# LEDpanel.net
KiCad netlist of a schematic drawn in EAGLE
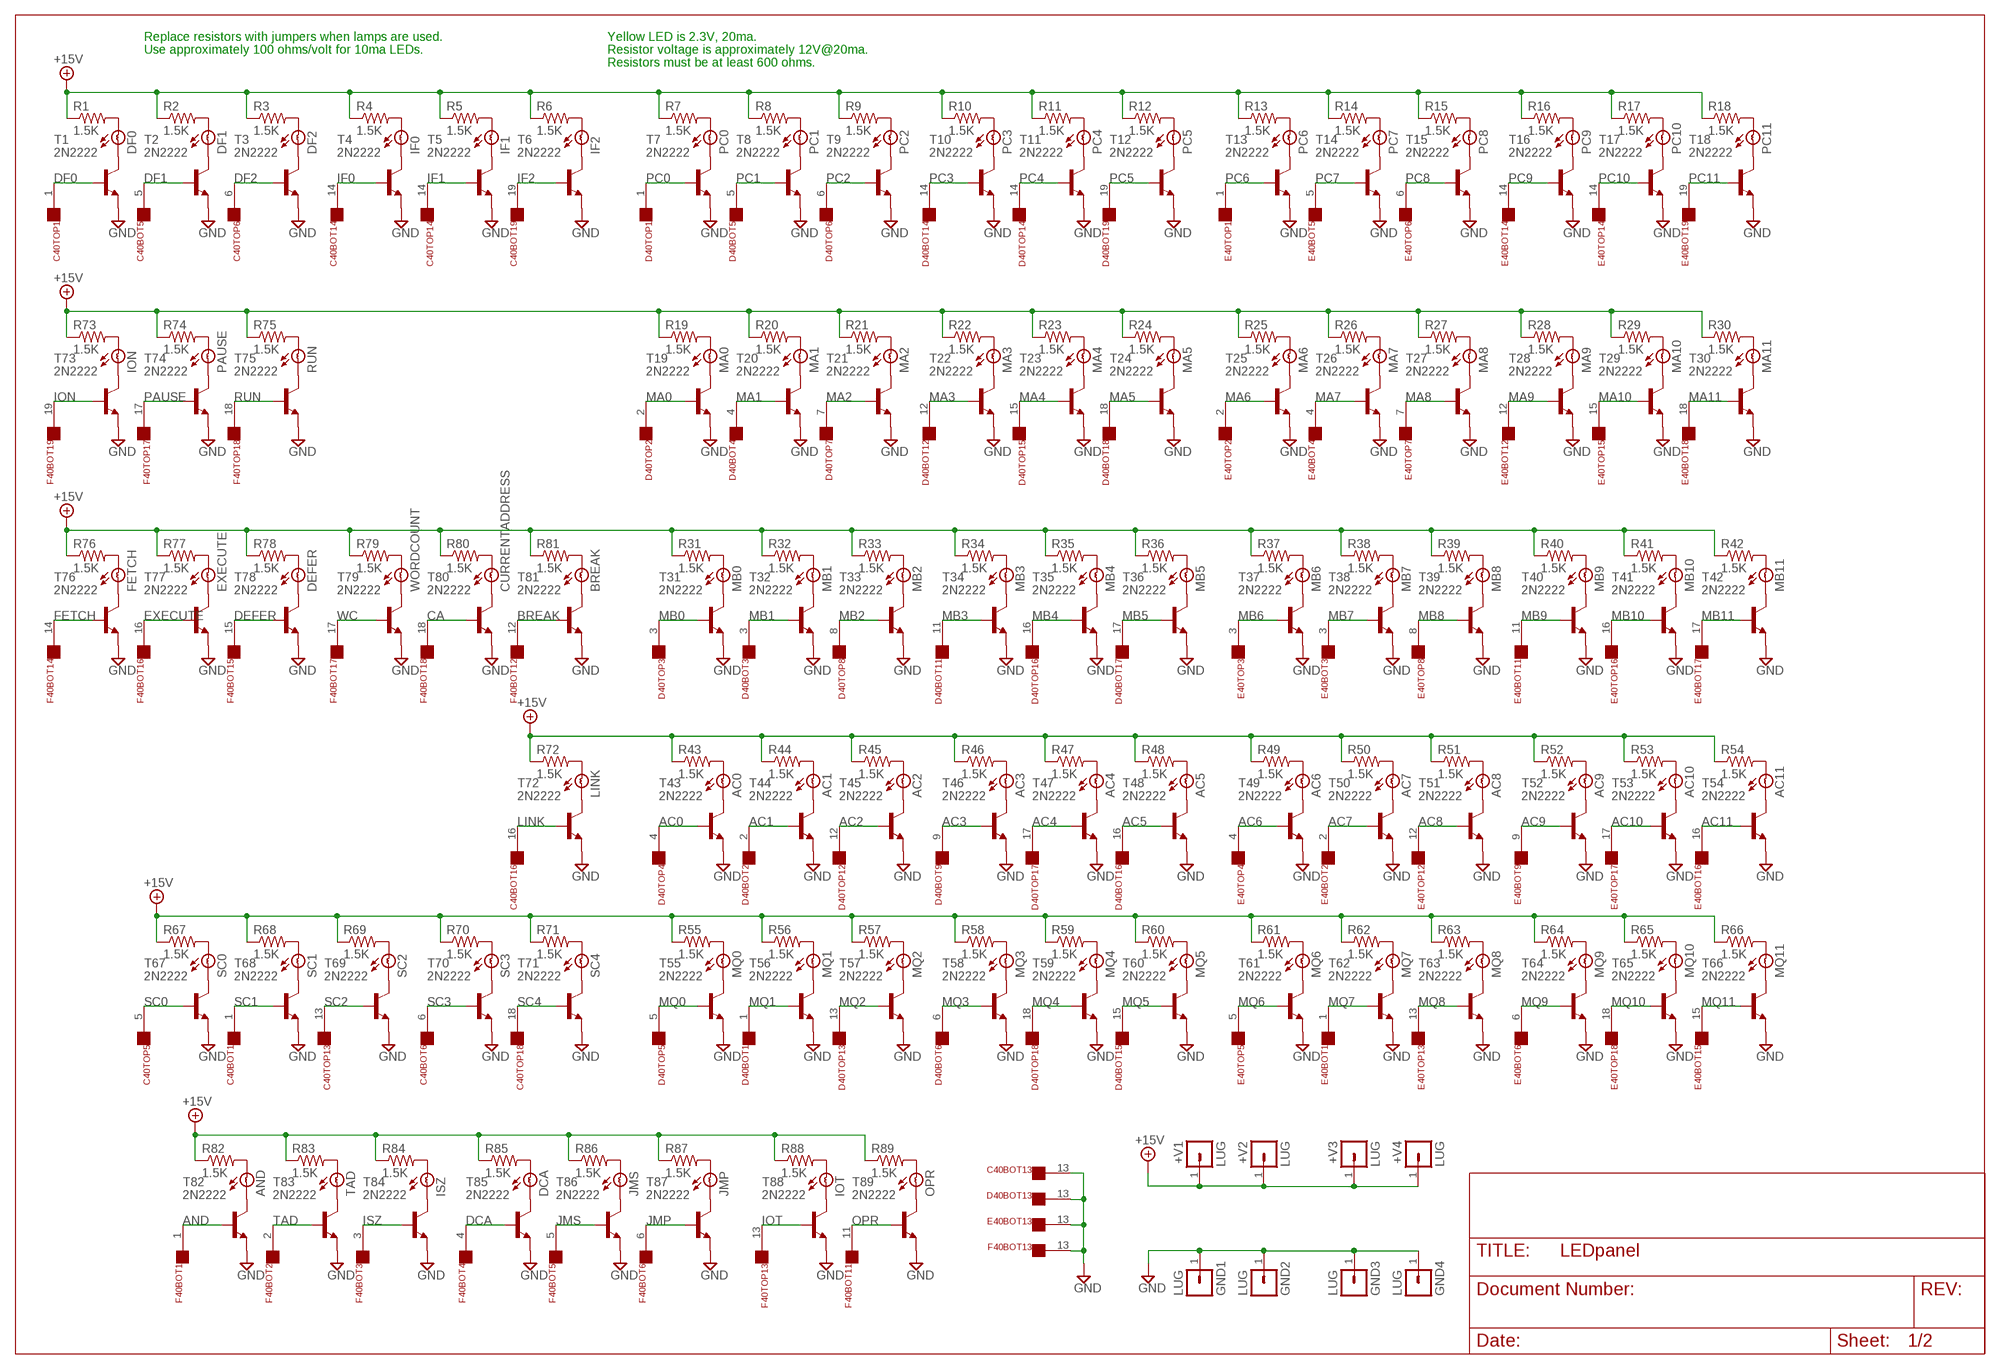
[diagram p0: schematic, sheet 1]
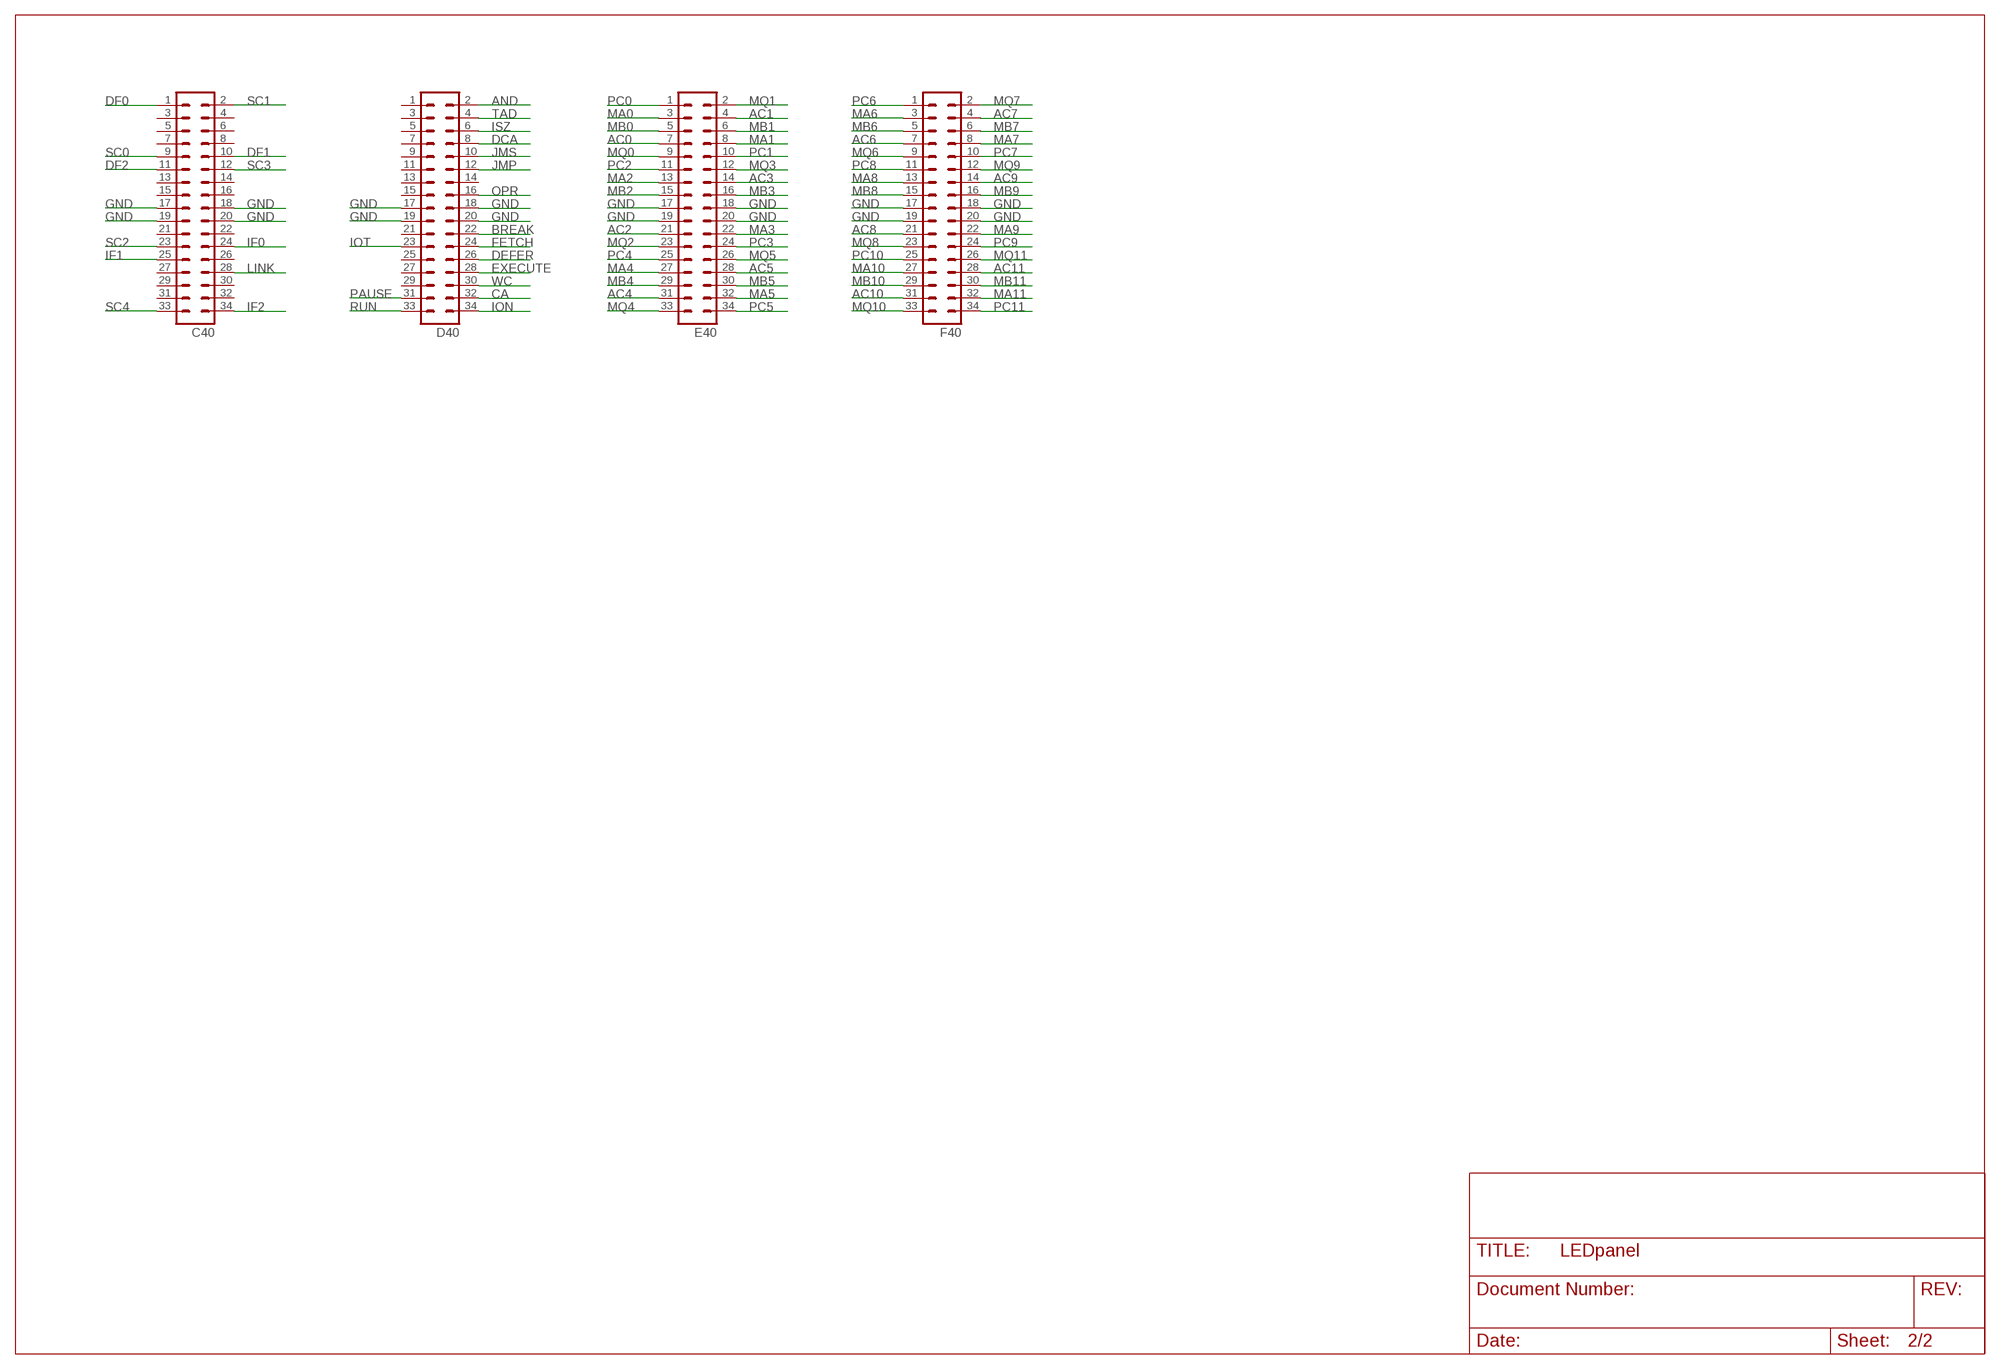
[diagram p1: schematic, sheet 2]

(export (version "E")
  (design (tool "Eeschema 10.0.6"))
  (components
    (comp (ref "+V1")
      (value "LUG")
      (footprint "eagle-import:SPADELUG")
      (libsource (lib "eagle-import") (part "LUG"))
    )
    (comp (ref "+V2")
      (value "LUG")
      (footprint "eagle-import:SPADELUG")
      (libsource (lib "eagle-import") (part "LUG"))
    )
    (comp (ref "+V3")
      (value "LUG")
      (footprint "eagle-import:SPADELUG")
      (libsource (lib "eagle-import") (part "LUG"))
    )
    (comp (ref "+V4")
      (value "LUG")
      (footprint "eagle-import:SPADELUG")
      (libsource (lib "eagle-import") (part "LUG"))
    )
    (comp (ref "AC0")
      (value "BULB")
      (footprint "eagle-import:BULB")
      (libsource (lib "eagle-import") (part "BULB"))
    )
    (comp (ref "AC1")
      (value "BULB")
      (footprint "eagle-import:BULB")
      (libsource (lib "eagle-import") (part "BULB"))
    )
    (comp (ref "AC2")
      (value "BULB")
      (footprint "eagle-import:BULB")
      (libsource (lib "eagle-import") (part "BULB"))
    )
    (comp (ref "AC3")
      (value "BULB")
      (footprint "eagle-import:BULB")
      (libsource (lib "eagle-import") (part "BULB"))
    )
    (comp (ref "AC4")
      (value "BULB")
      (footprint "eagle-import:BULB")
      (libsource (lib "eagle-import") (part "BULB"))
    )
    (comp (ref "AC5")
      (value "BULB")
      (footprint "eagle-import:BULB")
      (libsource (lib "eagle-import") (part "BULB"))
    )
    (comp (ref "AC6")
      (value "BULB")
      (footprint "eagle-import:BULB")
      (libsource (lib "eagle-import") (part "BULB"))
    )
    (comp (ref "AC7")
      (value "BULB")
      (footprint "eagle-import:BULB")
      (libsource (lib "eagle-import") (part "BULB"))
    )
    (comp (ref "AC8")
      (value "BULB")
      (footprint "eagle-import:BULB")
      (libsource (lib "eagle-import") (part "BULB"))
    )
    (comp (ref "AC9")
      (value "BULB")
      (footprint "eagle-import:BULB")
      (libsource (lib "eagle-import") (part "BULB"))
    )
    (comp (ref "AC10")
      (value "BULB")
      (footprint "eagle-import:BULB")
      (libsource (lib "eagle-import") (part "BULB"))
    )
    (comp (ref "AC11")
      (value "BULB")
      (footprint "eagle-import:BULB")
      (libsource (lib "eagle-import") (part "BULB"))
    )
    (comp (ref "AND")
      (value "BULB")
      (footprint "eagle-import:BULB")
      (libsource (lib "eagle-import") (part "BULB"))
    )
    (comp (ref "BREAK")
      (value "BULB")
      (footprint "eagle-import:BULB")
      (libsource (lib "eagle-import") (part "BULB"))
    )
    (comp (ref "C40BOT")
      (value "FLEX19")
      (footprint "eagle-import:FLEX19")
      (libsource (lib "eagle-import") (part "FLEX19"))
    )
    (comp (ref "C40TOP")
      (value "FLEX19")
      (footprint "eagle-import:FLEX19")
      (libsource (lib "eagle-import") (part "FLEX19"))
    )
    (comp (ref "CURRENTADDRESS")
      (value "BULB")
      (footprint "eagle-import:BULB")
      (libsource (lib "eagle-import") (part "BULB"))
    )
    (comp (ref "D40BOT")
      (value "FLEX19")
      (footprint "eagle-import:FLEX19")
      (libsource (lib "eagle-import") (part "FLEX19"))
    )
    (comp (ref "D40TOP")
      (value "FLEX19")
      (footprint "eagle-import:FLEX19")
      (libsource (lib "eagle-import") (part "FLEX19"))
    )
    (comp (ref "DCA")
      (value "BULB")
      (footprint "eagle-import:BULB")
      (libsource (lib "eagle-import") (part "BULB"))
    )
    (comp (ref "DEFER")
      (value "BULB")
      (footprint "eagle-import:BULB")
      (libsource (lib "eagle-import") (part "BULB"))
    )
    (comp (ref "DF0")
      (value "BULB")
      (footprint "eagle-import:BULB")
      (libsource (lib "eagle-import") (part "BULB"))
    )
    (comp (ref "DF1")
      (value "BULB")
      (footprint "eagle-import:BULB")
      (libsource (lib "eagle-import") (part "BULB"))
    )
    (comp (ref "DF2")
      (value "BULB")
      (footprint "eagle-import:BULB")
      (libsource (lib "eagle-import") (part "BULB"))
    )
    (comp (ref "E40BOT")
      (value "FLEX19")
      (footprint "eagle-import:FLEX19")
      (libsource (lib "eagle-import") (part "FLEX19"))
    )
    (comp (ref "E40TOP")
      (value "FLEX19")
      (footprint "eagle-import:FLEX19")
      (libsource (lib "eagle-import") (part "FLEX19"))
    )
    (comp (ref "EXECUTE")
      (value "BULB")
      (footprint "eagle-import:BULB")
      (libsource (lib "eagle-import") (part "BULB"))
    )
    (comp (ref "F40BOT")
      (value "FLEX19")
      (footprint "eagle-import:FLEX19")
      (libsource (lib "eagle-import") (part "FLEX19"))
    )
    (comp (ref "F40TOP")
      (value "FLEX19")
      (footprint "eagle-import:FLEX19")
      (libsource (lib "eagle-import") (part "FLEX19"))
    )
    (comp (ref "FETCH")
      (value "BULB")
      (footprint "eagle-import:BULB")
      (libsource (lib "eagle-import") (part "BULB"))
    )
    (comp (ref "GND1")
      (value "LUG")
      (footprint "eagle-import:SPADELUG")
      (libsource (lib "eagle-import") (part "LUG"))
    )
    (comp (ref "GND2")
      (value "LUG")
      (footprint "eagle-import:SPADELUG")
      (libsource (lib "eagle-import") (part "LUG"))
    )
    (comp (ref "GND3")
      (value "LUG")
      (footprint "eagle-import:SPADELUG")
      (libsource (lib "eagle-import") (part "LUG"))
    )
    (comp (ref "GND4")
      (value "LUG")
      (footprint "eagle-import:SPADELUG")
      (libsource (lib "eagle-import") (part "LUG"))
    )
    (comp (ref "IF0")
      (value "BULB")
      (footprint "eagle-import:BULB")
      (libsource (lib "eagle-import") (part "BULB"))
    )
    (comp (ref "IF1")
      (value "BULB")
      (footprint "eagle-import:BULB")
      (libsource (lib "eagle-import") (part "BULB"))
    )
    (comp (ref "IF2")
      (value "BULB")
      (footprint "eagle-import:BULB")
      (libsource (lib "eagle-import") (part "BULB"))
    )
    (comp (ref "ION")
      (value "BULB")
      (footprint "eagle-import:BULB")
      (libsource (lib "eagle-import") (part "BULB"))
    )
    (comp (ref "IOT")
      (value "BULB")
      (footprint "eagle-import:BULB")
      (libsource (lib "eagle-import") (part "BULB"))
    )
    (comp (ref "ISZ")
      (value "BULB")
      (footprint "eagle-import:BULB")
      (libsource (lib "eagle-import") (part "BULB"))
    )
    (comp (ref "JMP")
      (value "BULB")
      (footprint "eagle-import:BULB")
      (libsource (lib "eagle-import") (part "BULB"))
    )
    (comp (ref "JMS")
      (value "BULB")
      (footprint "eagle-import:BULB")
      (libsource (lib "eagle-import") (part "BULB"))
    )
    (comp (ref "LINK")
      (value "BULB")
      (footprint "eagle-import:BULB")
      (libsource (lib "eagle-import") (part "BULB"))
    )
    (comp (ref "MA0")
      (value "BULB")
      (footprint "eagle-import:BULB")
      (libsource (lib "eagle-import") (part "BULB"))
    )
    (comp (ref "MA1")
      (value "BULB")
      (footprint "eagle-import:BULB")
      (libsource (lib "eagle-import") (part "BULB"))
    )
    (comp (ref "MA2")
      (value "BULB")
      (footprint "eagle-import:BULB")
      (libsource (lib "eagle-import") (part "BULB"))
    )
    (comp (ref "MA3")
      (value "BULB")
      (footprint "eagle-import:BULB")
      (libsource (lib "eagle-import") (part "BULB"))
    )
    (comp (ref "MA4")
      (value "BULB")
      (footprint "eagle-import:BULB")
      (libsource (lib "eagle-import") (part "BULB"))
    )
    (comp (ref "MA5")
      (value "BULB")
      (footprint "eagle-import:BULB")
      (libsource (lib "eagle-import") (part "BULB"))
    )
    (comp (ref "MA6")
      (value "BULB")
      (footprint "eagle-import:BULB")
      (libsource (lib "eagle-import") (part "BULB"))
    )
    (comp (ref "MA7")
      (value "BULB")
      (footprint "eagle-import:BULB")
      (libsource (lib "eagle-import") (part "BULB"))
    )
    (comp (ref "MA8")
      (value "BULB")
      (footprint "eagle-import:BULB")
      (libsource (lib "eagle-import") (part "BULB"))
    )
    (comp (ref "MA9")
      (value "BULB")
      (footprint "eagle-import:BULB")
      (libsource (lib "eagle-import") (part "BULB"))
    )
    (comp (ref "MA10")
      (value "BULB")
      (footprint "eagle-import:BULB")
      (libsource (lib "eagle-import") (part "BULB"))
    )
    (comp (ref "MA11")
      (value "BULB")
      (footprint "eagle-import:BULB")
      (libsource (lib "eagle-import") (part "BULB"))
    )
    (comp (ref "MB0")
      (value "BULB")
      (footprint "eagle-import:BULB")
      (libsource (lib "eagle-import") (part "BULB"))
    )
    (comp (ref "MB1")
      (value "BULB")
      (footprint "eagle-import:BULB")
      (libsource (lib "eagle-import") (part "BULB"))
    )
    (comp (ref "MB2")
      (value "BULB")
      (footprint "eagle-import:BULB")
      (libsource (lib "eagle-import") (part "BULB"))
    )
    (comp (ref "MB3")
      (value "BULB")
      (footprint "eagle-import:BULB")
      (libsource (lib "eagle-import") (part "BULB"))
    )
    (comp (ref "MB4")
      (value "BULB")
      (footprint "eagle-import:BULB")
      (libsource (lib "eagle-import") (part "BULB"))
    )
    (comp (ref "MB5")
      (value "BULB")
      (footprint "eagle-import:BULB")
      (libsource (lib "eagle-import") (part "BULB"))
    )
    (comp (ref "MB6")
      (value "BULB")
      (footprint "eagle-import:BULB")
      (libsource (lib "eagle-import") (part "BULB"))
    )
    (comp (ref "MB7")
      (value "BULB")
      (footprint "eagle-import:BULB")
      (libsource (lib "eagle-import") (part "BULB"))
    )
    (comp (ref "MB8")
      (value "BULB")
      (footprint "eagle-import:BULB")
      (libsource (lib "eagle-import") (part "BULB"))
    )
    (comp (ref "MB9")
      (value "BULB")
      (footprint "eagle-import:BULB")
      (libsource (lib "eagle-import") (part "BULB"))
    )
    (comp (ref "MB10")
      (value "BULB")
      (footprint "eagle-import:BULB")
      (libsource (lib "eagle-import") (part "BULB"))
    )
    (comp (ref "MB11")
      (value "BULB")
      (footprint "eagle-import:BULB")
      (libsource (lib "eagle-import") (part "BULB"))
    )
    (comp (ref "MQ0")
      (value "BULB")
      (footprint "eagle-import:BULB")
      (libsource (lib "eagle-import") (part "BULB"))
    )
    (comp (ref "MQ1")
      (value "BULB")
      (footprint "eagle-import:BULB")
      (libsource (lib "eagle-import") (part "BULB"))
    )
    (comp (ref "MQ2")
      (value "BULB")
      (footprint "eagle-import:BULB")
      (libsource (lib "eagle-import") (part "BULB"))
    )
    (comp (ref "MQ3")
      (value "BULB")
      (footprint "eagle-import:BULB")
      (libsource (lib "eagle-import") (part "BULB"))
    )
    (comp (ref "MQ4")
      (value "BULB")
      (footprint "eagle-import:BULB")
      (libsource (lib "eagle-import") (part "BULB"))
    )
    (comp (ref "MQ5")
      (value "BULB")
      (footprint "eagle-import:BULB")
      (libsource (lib "eagle-import") (part "BULB"))
    )
    (comp (ref "MQ6")
      (value "BULB")
      (footprint "eagle-import:BULB")
      (libsource (lib "eagle-import") (part "BULB"))
    )
    (comp (ref "MQ7")
      (value "BULB")
      (footprint "eagle-import:BULB")
      (libsource (lib "eagle-import") (part "BULB"))
    )
    (comp (ref "MQ8")
      (value "BULB")
      (footprint "eagle-import:BULB")
      (libsource (lib "eagle-import") (part "BULB"))
    )
    (comp (ref "MQ9")
      (value "BULB")
      (footprint "eagle-import:BULB")
      (libsource (lib "eagle-import") (part "BULB"))
    )
    (comp (ref "MQ10")
      (value "BULB")
      (footprint "eagle-import:BULB")
      (libsource (lib "eagle-import") (part "BULB"))
    )
    (comp (ref "MQ11")
      (value "BULB")
      (footprint "eagle-import:BULB")
      (libsource (lib "eagle-import") (part "BULB"))
    )
    (comp (ref "OPR")
      (value "BULB")
      (footprint "eagle-import:BULB")
      (libsource (lib "eagle-import") (part "BULB"))
    )
    (comp (ref "PAUSE")
      (value "BULB")
      (footprint "eagle-import:BULB")
      (libsource (lib "eagle-import") (part "BULB"))
    )
    (comp (ref "PC0")
      (value "BULB")
      (footprint "eagle-import:BULB")
      (libsource (lib "eagle-import") (part "BULB"))
    )
    (comp (ref "PC1")
      (value "BULB")
      (footprint "eagle-import:BULB")
      (libsource (lib "eagle-import") (part "BULB"))
    )
    (comp (ref "PC2")
      (value "BULB")
      (footprint "eagle-import:BULB")
      (libsource (lib "eagle-import") (part "BULB"))
    )
    (comp (ref "PC3")
      (value "BULB")
      (footprint "eagle-import:BULB")
      (libsource (lib "eagle-import") (part "BULB"))
    )
    (comp (ref "PC4")
      (value "BULB")
      (footprint "eagle-import:BULB")
      (libsource (lib "eagle-import") (part "BULB"))
    )
    (comp (ref "PC5")
      (value "BULB")
      (footprint "eagle-import:BULB")
      (libsource (lib "eagle-import") (part "BULB"))
    )
    (comp (ref "PC6")
      (value "BULB")
      (footprint "eagle-import:BULB")
      (libsource (lib "eagle-import") (part "BULB"))
    )
    (comp (ref "PC7")
      (value "BULB")
      (footprint "eagle-import:BULB")
      (libsource (lib "eagle-import") (part "BULB"))
    )
    (comp (ref "PC8")
      (value "BULB")
      (footprint "eagle-import:BULB")
      (libsource (lib "eagle-import") (part "BULB"))
    )
    (comp (ref "PC9")
      (value "BULB")
      (footprint "eagle-import:BULB")
      (libsource (lib "eagle-import") (part "BULB"))
    )
    (comp (ref "PC10")
      (value "BULB")
      (footprint "eagle-import:BULB")
      (libsource (lib "eagle-import") (part "BULB"))
    )
    (comp (ref "PC11")
      (value "BULB")
      (footprint "eagle-import:BULB")
      (libsource (lib "eagle-import") (part "BULB"))
    )
    (comp (ref "R1")
      (value "1.5K")
      (footprint "eagle-import:0207_10")
      (libsource (lib "eagle-import") (part "R-US_0207/10"))
    )
    (comp (ref "R2")
      (value "1.5K")
      (footprint "eagle-import:0207_10")
      (libsource (lib "eagle-import") (part "R-US_0207/10"))
    )
    (comp (ref "R3")
      (value "1.5K")
      (footprint "eagle-import:0207_10")
      (libsource (lib "eagle-import") (part "R-US_0207/10"))
    )
    (comp (ref "R4")
      (value "1.5K")
      (footprint "eagle-import:0207_10")
      (libsource (lib "eagle-import") (part "R-US_0207/10"))
    )
    (comp (ref "R5")
      (value "1.5K")
      (footprint "eagle-import:0207_10")
      (libsource (lib "eagle-import") (part "R-US_0207/10"))
    )
    (comp (ref "R6")
      (value "1.5K")
      (footprint "eagle-import:0207_10")
      (libsource (lib "eagle-import") (part "R-US_0207/10"))
    )
    (comp (ref "R7")
      (value "1.5K")
      (footprint "eagle-import:0207_10")
      (libsource (lib "eagle-import") (part "R-US_0207/10"))
    )
    (comp (ref "R8")
      (value "1.5K")
      (footprint "eagle-import:0207_10")
      (libsource (lib "eagle-import") (part "R-US_0207/10"))
    )
    (comp (ref "R9")
      (value "1.5K")
      (footprint "eagle-import:0207_10")
      (libsource (lib "eagle-import") (part "R-US_0207/10"))
    )
    (comp (ref "R10")
      (value "1.5K")
      (footprint "eagle-import:0207_10")
      (libsource (lib "eagle-import") (part "R-US_0207/10"))
    )
    (comp (ref "R11")
      (value "1.5K")
      (footprint "eagle-import:0207_10")
      (libsource (lib "eagle-import") (part "R-US_0207/10"))
    )
    (comp (ref "R12")
      (value "1.5K")
      (footprint "eagle-import:0207_10")
      (libsource (lib "eagle-import") (part "R-US_0207/10"))
    )
    (comp (ref "R13")
      (value "1.5K")
      (footprint "eagle-import:0207_10")
      (libsource (lib "eagle-import") (part "R-US_0207/10"))
    )
    (comp (ref "R14")
      (value "1.5K")
      (footprint "eagle-import:0207_10")
      (libsource (lib "eagle-import") (part "R-US_0207/10"))
    )
    (comp (ref "R15")
      (value "1.5K")
      (footprint "eagle-import:0207_10")
      (libsource (lib "eagle-import") (part "R-US_0207/10"))
    )
    (comp (ref "R16")
      (value "1.5K")
      (footprint "eagle-import:0207_10")
      (libsource (lib "eagle-import") (part "R-US_0207/10"))
    )
    (comp (ref "R17")
      (value "1.5K")
      (footprint "eagle-import:0207_10")
      (libsource (lib "eagle-import") (part "R-US_0207/10"))
    )
    (comp (ref "R18")
      (value "1.5K")
      (footprint "eagle-import:0207_10")
      (libsource (lib "eagle-import") (part "R-US_0207/10"))
    )
    (comp (ref "R19")
      (value "1.5K")
      (footprint "eagle-import:0207_10")
      (libsource (lib "eagle-import") (part "R-US_0207/10"))
    )
    (comp (ref "R20")
      (value "1.5K")
      (footprint "eagle-import:0207_10")
      (libsource (lib "eagle-import") (part "R-US_0207/10"))
    )
    (comp (ref "R21")
      (value "1.5K")
      (footprint "eagle-import:0207_10")
      (libsource (lib "eagle-import") (part "R-US_0207/10"))
    )
    (comp (ref "R22")
      (value "1.5K")
      (footprint "eagle-import:0207_10")
      (libsource (lib "eagle-import") (part "R-US_0207/10"))
    )
    (comp (ref "R23")
      (value "1.5K")
      (footprint "eagle-import:0207_10")
      (libsource (lib "eagle-import") (part "R-US_0207/10"))
    )
    (comp (ref "R24")
      (value "1.5K")
      (footprint "eagle-import:0207_10")
      (libsource (lib "eagle-import") (part "R-US_0207/10"))
    )
    (comp (ref "R25")
      (value "1.5K")
      (footprint "eagle-import:0207_10")
      (libsource (lib "eagle-import") (part "R-US_0207/10"))
    )
    (comp (ref "R26")
      (value "1.5K")
      (footprint "eagle-import:0207_10")
      (libsource (lib "eagle-import") (part "R-US_0207/10"))
    )
    (comp (ref "R27")
      (value "1.5K")
      (footprint "eagle-import:0207_10")
      (libsource (lib "eagle-import") (part "R-US_0207/10"))
    )
    (comp (ref "R28")
      (value "1.5K")
      (footprint "eagle-import:0207_10")
      (libsource (lib "eagle-import") (part "R-US_0207/10"))
    )
    (comp (ref "R29")
      (value "1.5K")
      (footprint "eagle-import:0207_10")
      (libsource (lib "eagle-import") (part "R-US_0207/10"))
    )
    (comp (ref "R30")
      (value "1.5K")
      (footprint "eagle-import:0207_10")
      (libsource (lib "eagle-import") (part "R-US_0207/10"))
    )
    (comp (ref "R31")
      (value "1.5K")
      (footprint "eagle-import:0207_10")
      (libsource (lib "eagle-import") (part "R-US_0207/10"))
    )
    (comp (ref "R32")
      (value "1.5K")
      (footprint "eagle-import:0207_10")
      (libsource (lib "eagle-import") (part "R-US_0207/10"))
    )
    (comp (ref "R33")
      (value "1.5K")
      (footprint "eagle-import:0207_10")
      (libsource (lib "eagle-import") (part "R-US_0207/10"))
    )
    (comp (ref "R34")
      (value "1.5K")
      (footprint "eagle-import:0207_10")
      (libsource (lib "eagle-import") (part "R-US_0207/10"))
    )
    (comp (ref "R35")
      (value "1.5K")
      (footprint "eagle-import:0207_10")
      (libsource (lib "eagle-import") (part "R-US_0207/10"))
    )
    (comp (ref "R36")
      (value "1.5K")
      (footprint "eagle-import:0207_10")
      (libsource (lib "eagle-import") (part "R-US_0207/10"))
    )
    (comp (ref "R37")
      (value "1.5K")
      (footprint "eagle-import:0207_10")
      (libsource (lib "eagle-import") (part "R-US_0207/10"))
    )
    (comp (ref "R38")
      (value "1.5K")
      (footprint "eagle-import:0207_10")
      (libsource (lib "eagle-import") (part "R-US_0207/10"))
    )
    (comp (ref "R39")
      (value "1.5K")
      (footprint "eagle-import:0207_10")
      (libsource (lib "eagle-import") (part "R-US_0207/10"))
    )
    (comp (ref "R40")
      (value "1.5K")
      (footprint "eagle-import:0207_10")
      (libsource (lib "eagle-import") (part "R-US_0207/10"))
    )
    (comp (ref "R41")
      (value "1.5K")
      (footprint "eagle-import:0207_10")
      (libsource (lib "eagle-import") (part "R-US_0207/10"))
    )
    (comp (ref "R42")
      (value "1.5K")
      (footprint "eagle-import:0207_10")
      (libsource (lib "eagle-import") (part "R-US_0207/10"))
    )
    (comp (ref "R43")
      (value "1.5K")
      (footprint "eagle-import:0207_10")
      (libsource (lib "eagle-import") (part "R-US_0207/10"))
    )
    (comp (ref "R44")
      (value "1.5K")
      (footprint "eagle-import:0207_10")
      (libsource (lib "eagle-import") (part "R-US_0207/10"))
    )
    (comp (ref "R45")
      (value "1.5K")
      (footprint "eagle-import:0207_10")
      (libsource (lib "eagle-import") (part "R-US_0207/10"))
    )
    (comp (ref "R46")
      (value "1.5K")
      (footprint "eagle-import:0207_10")
      (libsource (lib "eagle-import") (part "R-US_0207/10"))
    )
    (comp (ref "R47")
      (value "1.5K")
      (footprint "eagle-import:0207_10")
      (libsource (lib "eagle-import") (part "R-US_0207/10"))
    )
    (comp (ref "R48")
      (value "1.5K")
      (footprint "eagle-import:0207_10")
      (libsource (lib "eagle-import") (part "R-US_0207/10"))
    )
    (comp (ref "R49")
      (value "1.5K")
      (footprint "eagle-import:0207_10")
      (libsource (lib "eagle-import") (part "R-US_0207/10"))
    )
    (comp (ref "R50")
      (value "1.5K")
      (footprint "eagle-import:0207_10")
      (libsource (lib "eagle-import") (part "R-US_0207/10"))
    )
    (comp (ref "R51")
      (value "1.5K")
      (footprint "eagle-import:0207_10")
      (libsource (lib "eagle-import") (part "R-US_0207/10"))
    )
    (comp (ref "R52")
      (value "1.5K")
      (footprint "eagle-import:0207_10")
      (libsource (lib "eagle-import") (part "R-US_0207/10"))
    )
    (comp (ref "R53")
      (value "1.5K")
      (footprint "eagle-import:0207_10")
      (libsource (lib "eagle-import") (part "R-US_0207/10"))
    )
    (comp (ref "R54")
      (value "1.5K")
      (footprint "eagle-import:0207_10")
      (libsource (lib "eagle-import") (part "R-US_0207/10"))
    )
    (comp (ref "R55")
      (value "1.5K")
      (footprint "eagle-import:0207_10")
      (libsource (lib "eagle-import") (part "R-US_0207/10"))
    )
    (comp (ref "R56")
      (value "1.5K")
      (footprint "eagle-import:0207_10")
      (libsource (lib "eagle-import") (part "R-US_0207/10"))
    )
    (comp (ref "R57")
      (value "1.5K")
      (footprint "eagle-import:0207_10")
      (libsource (lib "eagle-import") (part "R-US_0207/10"))
    )
    (comp (ref "R58")
      (value "1.5K")
      (footprint "eagle-import:0207_10")
      (libsource (lib "eagle-import") (part "R-US_0207/10"))
    )
    (comp (ref "R59")
      (value "1.5K")
      (footprint "eagle-import:0207_10")
      (libsource (lib "eagle-import") (part "R-US_0207/10"))
    )
    (comp (ref "R60")
      (value "1.5K")
      (footprint "eagle-import:0207_10")
      (libsource (lib "eagle-import") (part "R-US_0207/10"))
    )
    (comp (ref "R61")
      (value "1.5K")
      (footprint "eagle-import:0207_10")
      (libsource (lib "eagle-import") (part "R-US_0207/10"))
    )
    (comp (ref "R62")
      (value "1.5K")
      (footprint "eagle-import:0207_10")
      (libsource (lib "eagle-import") (part "R-US_0207/10"))
    )
    (comp (ref "R63")
      (value "1.5K")
      (footprint "eagle-import:0207_10")
      (libsource (lib "eagle-import") (part "R-US_0207/10"))
    )
    (comp (ref "R64")
      (value "1.5K")
      (footprint "eagle-import:0207_10")
      (libsource (lib "eagle-import") (part "R-US_0207/10"))
    )
    (comp (ref "R65")
      (value "1.5K")
      (footprint "eagle-import:0207_10")
      (libsource (lib "eagle-import") (part "R-US_0207/10"))
    )
    (comp (ref "R66")
      (value "1.5K")
      (footprint "eagle-import:0207_10")
      (libsource (lib "eagle-import") (part "R-US_0207/10"))
    )
    (comp (ref "R67")
      (value "1.5K")
      (footprint "eagle-import:0207_10")
      (libsource (lib "eagle-import") (part "R-US_0207/10"))
    )
    (comp (ref "R68")
      (value "1.5K")
      (footprint "eagle-import:0207_10")
      (libsource (lib "eagle-import") (part "R-US_0207/10"))
    )
    (comp (ref "R69")
      (value "1.5K")
      (footprint "eagle-import:0207_10")
      (libsource (lib "eagle-import") (part "R-US_0207/10"))
    )
    (comp (ref "R70")
      (value "1.5K")
      (footprint "eagle-import:0207_10")
      (libsource (lib "eagle-import") (part "R-US_0207/10"))
    )
    (comp (ref "R71")
      (value "1.5K")
      (footprint "eagle-import:0207_10")
      (libsource (lib "eagle-import") (part "R-US_0207/10"))
    )
    (comp (ref "R72")
      (value "1.5K")
      (footprint "eagle-import:0207_10")
      (libsource (lib "eagle-import") (part "R-US_0207/10"))
    )
    (comp (ref "R73")
      (value "1.5K")
      (footprint "eagle-import:0207_10")
      (libsource (lib "eagle-import") (part "R-US_0207/10"))
    )
    (comp (ref "R74")
      (value "1.5K")
      (footprint "eagle-import:0207_10")
      (libsource (lib "eagle-import") (part "R-US_0207/10"))
    )
    (comp (ref "R75")
      (value "1.5K")
      (footprint "eagle-import:0207_10")
      (libsource (lib "eagle-import") (part "R-US_0207/10"))
    )
    (comp (ref "R76")
      (value "1.5K")
      (footprint "eagle-import:0207_10")
      (libsource (lib "eagle-import") (part "R-US_0207/10"))
    )
    (comp (ref "R77")
      (value "1.5K")
      (footprint "eagle-import:0207_10")
      (libsource (lib "eagle-import") (part "R-US_0207/10"))
    )
    (comp (ref "R78")
      (value "1.5K")
      (footprint "eagle-import:0207_10")
      (libsource (lib "eagle-import") (part "R-US_0207/10"))
    )
    (comp (ref "R79")
      (value "1.5K")
      (footprint "eagle-import:0207_10")
      (libsource (lib "eagle-import") (part "R-US_0207/10"))
    )
    (comp (ref "R80")
      (value "1.5K")
      (footprint "eagle-import:0207_10")
      (libsource (lib "eagle-import") (part "R-US_0207/10"))
    )
    (comp (ref "R81")
      (value "1.5K")
      (footprint "eagle-import:0207_10")
      (libsource (lib "eagle-import") (part "R-US_0207/10"))
    )
    (comp (ref "R82")
      (value "1.5K")
      (footprint "eagle-import:0207_10")
      (libsource (lib "eagle-import") (part "R-US_0207/10"))
    )
    (comp (ref "R83")
      (value "1.5K")
      (footprint "eagle-import:0207_10")
      (libsource (lib "eagle-import") (part "R-US_0207/10"))
    )
    (comp (ref "R84")
      (value "1.5K")
      (footprint "eagle-import:0207_10")
      (libsource (lib "eagle-import") (part "R-US_0207/10"))
    )
    (comp (ref "R85")
      (value "1.5K")
      (footprint "eagle-import:0207_10")
      (libsource (lib "eagle-import") (part "R-US_0207/10"))
    )
    (comp (ref "R86")
      (value "1.5K")
      (footprint "eagle-import:0207_10")
      (libsource (lib "eagle-import") (part "R-US_0207/10"))
    )
    (comp (ref "R87")
      (value "1.5K")
      (footprint "eagle-import:0207_10")
      (libsource (lib "eagle-import") (part "R-US_0207/10"))
    )
    (comp (ref "R88")
      (value "1.5K")
      (footprint "eagle-import:0207_10")
      (libsource (lib "eagle-import") (part "R-US_0207/10"))
    )
    (comp (ref "R89")
      (value "1.5K")
      (footprint "eagle-import:0207_10")
      (libsource (lib "eagle-import") (part "R-US_0207/10"))
    )
    (comp (ref "RUN")
      (value "BULB")
      (footprint "eagle-import:BULB")
      (libsource (lib "eagle-import") (part "BULB"))
    )
    (comp (ref "SC0")
      (value "BULB")
      (footprint "eagle-import:BULB")
      (libsource (lib "eagle-import") (part "BULB"))
    )
    (comp (ref "SC1")
      (value "BULB")
      (footprint "eagle-import:BULB")
      (libsource (lib "eagle-import") (part "BULB"))
    )
    (comp (ref "SC2")
      (value "BULB")
      (footprint "eagle-import:BULB")
      (libsource (lib "eagle-import") (part "BULB"))
    )
    (comp (ref "SC3")
      (value "BULB")
      (footprint "eagle-import:BULB")
      (libsource (lib "eagle-import") (part "BULB"))
    )
    (comp (ref "SC4")
      (value "BULB")
      (footprint "eagle-import:BULB")
      (libsource (lib "eagle-import") (part "BULB"))
    )
    (comp (ref "T1")
      (value "2N2222")
      (footprint "eagle-import:TO92")
      (libsource (lib "eagle-import") (part "-NPN-TO92"))
    )
    (comp (ref "T2")
      (value "2N2222")
      (footprint "eagle-import:TO92")
      (libsource (lib "eagle-import") (part "-NPN-TO92"))
    )
    (comp (ref "T3")
      (value "2N2222")
      (footprint "eagle-import:TO92")
      (libsource (lib "eagle-import") (part "-NPN-TO92"))
    )
    (comp (ref "T4")
      (value "2N2222")
      (footprint "eagle-import:TO92")
      (libsource (lib "eagle-import") (part "-NPN-TO92"))
    )
    (comp (ref "T5")
      (value "2N2222")
      (footprint "eagle-import:TO92")
      (libsource (lib "eagle-import") (part "-NPN-TO92"))
    )
    (comp (ref "T6")
      (value "2N2222")
      (footprint "eagle-import:TO92")
      (libsource (lib "eagle-import") (part "-NPN-TO92"))
    )
    (comp (ref "T7")
      (value "2N2222")
      (footprint "eagle-import:TO92")
      (libsource (lib "eagle-import") (part "-NPN-TO92"))
    )
    (comp (ref "T8")
      (value "2N2222")
      (footprint "eagle-import:TO92")
      (libsource (lib "eagle-import") (part "-NPN-TO92"))
    )
    (comp (ref "T9")
      (value "2N2222")
      (footprint "eagle-import:TO92")
      (libsource (lib "eagle-import") (part "-NPN-TO92"))
    )
    (comp (ref "T10")
      (value "2N2222")
      (footprint "eagle-import:TO92")
      (libsource (lib "eagle-import") (part "-NPN-TO92"))
    )
    (comp (ref "T11")
      (value "2N2222")
      (footprint "eagle-import:TO92")
      (libsource (lib "eagle-import") (part "-NPN-TO92"))
    )
    (comp (ref "T12")
      (value "2N2222")
      (footprint "eagle-import:TO92")
      (libsource (lib "eagle-import") (part "-NPN-TO92"))
    )
    (comp (ref "T13")
      (value "2N2222")
      (footprint "eagle-import:TO92")
      (libsource (lib "eagle-import") (part "-NPN-TO92"))
    )
    (comp (ref "T14")
      (value "2N2222")
      (footprint "eagle-import:TO92")
      (libsource (lib "eagle-import") (part "-NPN-TO92"))
    )
    (comp (ref "T15")
      (value "2N2222")
      (footprint "eagle-import:TO92")
      (libsource (lib "eagle-import") (part "-NPN-TO92"))
    )
    (comp (ref "T16")
      (value "2N2222")
      (footprint "eagle-import:TO92")
      (libsource (lib "eagle-import") (part "-NPN-TO92"))
    )
    (comp (ref "T17")
      (value "2N2222")
      (footprint "eagle-import:TO92")
      (libsource (lib "eagle-import") (part "-NPN-TO92"))
    )
    (comp (ref "T18")
      (value "2N2222")
      (footprint "eagle-import:TO92")
      (libsource (lib "eagle-import") (part "-NPN-TO92"))
    )
    (comp (ref "T19")
      (value "2N2222")
      (footprint "eagle-import:TO92")
      (libsource (lib "eagle-import") (part "-NPN-TO92"))
    )
    (comp (ref "T20")
      (value "2N2222")
      (footprint "eagle-import:TO92")
      (libsource (lib "eagle-import") (part "-NPN-TO92"))
    )
    (comp (ref "T21")
      (value "2N2222")
      (footprint "eagle-import:TO92")
      (libsource (lib "eagle-import") (part "-NPN-TO92"))
    )
    (comp (ref "T22")
      (value "2N2222")
      (footprint "eagle-import:TO92")
      (libsource (lib "eagle-import") (part "-NPN-TO92"))
    )
    (comp (ref "T23")
      (value "2N2222")
      (footprint "eagle-import:TO92")
      (libsource (lib "eagle-import") (part "-NPN-TO92"))
    )
    (comp (ref "T24")
      (value "2N2222")
      (footprint "eagle-import:TO92")
      (libsource (lib "eagle-import") (part "-NPN-TO92"))
    )
    (comp (ref "T25")
      (value "2N2222")
      (footprint "eagle-import:TO92")
      (libsource (lib "eagle-import") (part "-NPN-TO92"))
    )
    (comp (ref "T26")
      (value "2N2222")
      (footprint "eagle-import:TO92")
      (libsource (lib "eagle-import") (part "-NPN-TO92"))
    )
    (comp (ref "T27")
      (value "2N2222")
      (footprint "eagle-import:TO92")
      (libsource (lib "eagle-import") (part "-NPN-TO92"))
    )
    (comp (ref "T28")
      (value "2N2222")
      (footprint "eagle-import:TO92")
      (libsource (lib "eagle-import") (part "-NPN-TO92"))
    )
    (comp (ref "T29")
      (value "2N2222")
      (footprint "eagle-import:TO92")
      (libsource (lib "eagle-import") (part "-NPN-TO92"))
    )
    (comp (ref "T30")
      (value "2N2222")
      (footprint "eagle-import:TO92")
      (libsource (lib "eagle-import") (part "-NPN-TO92"))
    )
    (comp (ref "T31")
      (value "2N2222")
      (footprint "eagle-import:TO92")
      (libsource (lib "eagle-import") (part "-NPN-TO92"))
    )
    (comp (ref "T32")
      (value "2N2222")
      (footprint "eagle-import:TO92")
      (libsource (lib "eagle-import") (part "-NPN-TO92"))
    )
    (comp (ref "T33")
      (value "2N2222")
      (footprint "eagle-import:TO92")
      (libsource (lib "eagle-import") (part "-NPN-TO92"))
    )
    (comp (ref "T34")
      (value "2N2222")
      (footprint "eagle-import:TO92")
      (libsource (lib "eagle-import") (part "-NPN-TO92"))
    )
    (comp (ref "T35")
      (value "2N2222")
      (footprint "eagle-import:TO92")
      (libsource (lib "eagle-import") (part "-NPN-TO92"))
    )
    (comp (ref "T36")
      (value "2N2222")
      (footprint "eagle-import:TO92")
      (libsource (lib "eagle-import") (part "-NPN-TO92"))
    )
    (comp (ref "T37")
      (value "2N2222")
      (footprint "eagle-import:TO92")
      (libsource (lib "eagle-import") (part "-NPN-TO92"))
    )
    (comp (ref "T38")
      (value "2N2222")
      (footprint "eagle-import:TO92")
      (libsource (lib "eagle-import") (part "-NPN-TO92"))
    )
    (comp (ref "T39")
      (value "2N2222")
      (footprint "eagle-import:TO92")
      (libsource (lib "eagle-import") (part "-NPN-TO92"))
    )
    (comp (ref "T40")
      (value "2N2222")
      (footprint "eagle-import:TO92")
      (libsource (lib "eagle-import") (part "-NPN-TO92"))
    )
    (comp (ref "T41")
      (value "2N2222")
      (footprint "eagle-import:TO92")
      (libsource (lib "eagle-import") (part "-NPN-TO92"))
    )
    (comp (ref "T42")
      (value "2N2222")
      (footprint "eagle-import:TO92")
      (libsource (lib "eagle-import") (part "-NPN-TO92"))
    )
    (comp (ref "T43")
      (value "2N2222")
      (footprint "eagle-import:TO92")
      (libsource (lib "eagle-import") (part "-NPN-TO92"))
    )
    (comp (ref "T44")
      (value "2N2222")
      (footprint "eagle-import:TO92")
      (libsource (lib "eagle-import") (part "-NPN-TO92"))
    )
    (comp (ref "T45")
      (value "2N2222")
      (footprint "eagle-import:TO92")
      (libsource (lib "eagle-import") (part "-NPN-TO92"))
    )
    (comp (ref "T46")
      (value "2N2222")
      (footprint "eagle-import:TO92")
      (libsource (lib "eagle-import") (part "-NPN-TO92"))
    )
    (comp (ref "T47")
      (value "2N2222")
      (footprint "eagle-import:TO92")
      (libsource (lib "eagle-import") (part "-NPN-TO92"))
    )
    (comp (ref "T48")
      (value "2N2222")
      (footprint "eagle-import:TO92")
      (libsource (lib "eagle-import") (part "-NPN-TO92"))
    )
    (comp (ref "T49")
      (value "2N2222")
      (footprint "eagle-import:TO92")
      (libsource (lib "eagle-import") (part "-NPN-TO92"))
    )
    (comp (ref "T50")
      (value "2N2222")
      (footprint "eagle-import:TO92")
      (libsource (lib "eagle-import") (part "-NPN-TO92"))
    )
    (comp (ref "T51")
      (value "2N2222")
      (footprint "eagle-import:TO92")
      (libsource (lib "eagle-import") (part "-NPN-TO92"))
    )
    (comp (ref "T52")
      (value "2N2222")
      (footprint "eagle-import:TO92")
      (libsource (lib "eagle-import") (part "-NPN-TO92"))
    )
    (comp (ref "T53")
      (value "2N2222")
      (footprint "eagle-import:TO92")
      (libsource (lib "eagle-import") (part "-NPN-TO92"))
    )
    (comp (ref "T54")
      (value "2N2222")
      (footprint "eagle-import:TO92")
      (libsource (lib "eagle-import") (part "-NPN-TO92"))
    )
    (comp (ref "T55")
      (value "2N2222")
      (footprint "eagle-import:TO92")
      (libsource (lib "eagle-import") (part "-NPN-TO92"))
    )
    (comp (ref "T56")
      (value "2N2222")
      (footprint "eagle-import:TO92")
      (libsource (lib "eagle-import") (part "-NPN-TO92"))
    )
    (comp (ref "T57")
      (value "2N2222")
      (footprint "eagle-import:TO92")
      (libsource (lib "eagle-import") (part "-NPN-TO92"))
    )
    (comp (ref "T58")
      (value "2N2222")
      (footprint "eagle-import:TO92")
      (libsource (lib "eagle-import") (part "-NPN-TO92"))
    )
    (comp (ref "T59")
      (value "2N2222")
      (footprint "eagle-import:TO92")
      (libsource (lib "eagle-import") (part "-NPN-TO92"))
    )
    (comp (ref "T60")
      (value "2N2222")
      (footprint "eagle-import:TO92")
      (libsource (lib "eagle-import") (part "-NPN-TO92"))
    )
    (comp (ref "T61")
      (value "2N2222")
      (footprint "eagle-import:TO92")
      (libsource (lib "eagle-import") (part "-NPN-TO92"))
    )
    (comp (ref "T62")
      (value "2N2222")
      (footprint "eagle-import:TO92")
      (libsource (lib "eagle-import") (part "-NPN-TO92"))
    )
    (comp (ref "T63")
      (value "2N2222")
      (footprint "eagle-import:TO92")
      (libsource (lib "eagle-import") (part "-NPN-TO92"))
    )
    (comp (ref "T64")
      (value "2N2222")
      (footprint "eagle-import:TO92")
      (libsource (lib "eagle-import") (part "-NPN-TO92"))
    )
    (comp (ref "T65")
      (value "2N2222")
      (footprint "eagle-import:TO92")
      (libsource (lib "eagle-import") (part "-NPN-TO92"))
    )
    (comp (ref "T66")
      (value "2N2222")
      (footprint "eagle-import:TO92")
      (libsource (lib "eagle-import") (part "-NPN-TO92"))
    )
    (comp (ref "T67")
      (value "2N2222")
      (footprint "eagle-import:TO92")
      (libsource (lib "eagle-import") (part "-NPN-TO92"))
    )
    (comp (ref "T68")
      (value "2N2222")
      (footprint "eagle-import:TO92")
      (libsource (lib "eagle-import") (part "-NPN-TO92"))
    )
    (comp (ref "T69")
      (value "2N2222")
      (footprint "eagle-import:TO92")
      (libsource (lib "eagle-import") (part "-NPN-TO92"))
    )
    (comp (ref "T70")
      (value "2N2222")
      (footprint "eagle-import:TO92")
      (libsource (lib "eagle-import") (part "-NPN-TO92"))
    )
    (comp (ref "T71")
      (value "2N2222")
      (footprint "eagle-import:TO92")
      (libsource (lib "eagle-import") (part "-NPN-TO92"))
    )
    (comp (ref "T72")
      (value "2N2222")
      (footprint "eagle-import:TO92")
      (libsource (lib "eagle-import") (part "-NPN-TO92"))
    )
    (comp (ref "T73")
      (value "2N2222")
      (footprint "eagle-import:TO92")
      (libsource (lib "eagle-import") (part "-NPN-TO92"))
    )
    (comp (ref "T74")
      (value "2N2222")
      (footprint "eagle-import:TO92")
      (libsource (lib "eagle-import") (part "-NPN-TO92"))
    )
    (comp (ref "T75")
      (value "2N2222")
      (footprint "eagle-import:TO92")
      (libsource (lib "eagle-import") (part "-NPN-TO92"))
    )
    (comp (ref "T76")
      (value "2N2222")
      (footprint "eagle-import:TO92")
      (libsource (lib "eagle-import") (part "-NPN-TO92"))
    )
    (comp (ref "T77")
      (value "2N2222")
      (footprint "eagle-import:TO92")
      (libsource (lib "eagle-import") (part "-NPN-TO92"))
    )
    (comp (ref "T78")
      (value "2N2222")
      (footprint "eagle-import:TO92")
      (libsource (lib "eagle-import") (part "-NPN-TO92"))
    )
    (comp (ref "T79")
      (value "2N2222")
      (footprint "eagle-import:TO92")
      (libsource (lib "eagle-import") (part "-NPN-TO92"))
    )
    (comp (ref "T80")
      (value "2N2222")
      (footprint "eagle-import:TO92")
      (libsource (lib "eagle-import") (part "-NPN-TO92"))
    )
    (comp (ref "T81")
      (value "2N2222")
      (footprint "eagle-import:TO92")
      (libsource (lib "eagle-import") (part "-NPN-TO92"))
    )
    (comp (ref "T82")
      (value "2N2222")
      (footprint "eagle-import:TO92")
      (libsource (lib "eagle-import") (part "-NPN-TO92"))
    )
    (comp (ref "T83")
      (value "2N2222")
      (footprint "eagle-import:TO92")
      (libsource (lib "eagle-import") (part "-NPN-TO92"))
    )
    (comp (ref "T84")
      (value "2N2222")
      (footprint "eagle-import:TO92")
      (libsource (lib "eagle-import") (part "-NPN-TO92"))
    )
    (comp (ref "T85")
      (value "2N2222")
      (footprint "eagle-import:TO92")
      (libsource (lib "eagle-import") (part "-NPN-TO92"))
    )
    (comp (ref "T86")
      (value "2N2222")
      (footprint "eagle-import:TO92")
      (libsource (lib "eagle-import") (part "-NPN-TO92"))
    )
    (comp (ref "T87")
      (value "2N2222")
      (footprint "eagle-import:TO92")
      (libsource (lib "eagle-import") (part "-NPN-TO92"))
    )
    (comp (ref "T88")
      (value "2N2222")
      (footprint "eagle-import:TO92")
      (libsource (lib "eagle-import") (part "-NPN-TO92"))
    )
    (comp (ref "T89")
      (value "2N2222")
      (footprint "eagle-import:TO92")
      (libsource (lib "eagle-import") (part "-NPN-TO92"))
    )
    (comp (ref "TAD")
      (value "BULB")
      (footprint "eagle-import:BULB")
      (libsource (lib "eagle-import") (part "BULB"))
    )
    (comp (ref "WORDCOUNT")
      (value "BULB")
      (footprint "eagle-import:BULB")
      (libsource (lib "eagle-import") (part "BULB"))
    )
    (comp (ref "C40")
      (value "MA17-2")
      (footprint "eagle-import:MA17-2")
      (libsource (lib "eagle-import") (part "MA17-2"))
    )
    (comp (ref "D40")
      (value "MA17-2")
      (footprint "eagle-import:MA17-2")
      (libsource (lib "eagle-import") (part "MA17-2"))
    )
    (comp (ref "E40")
      (value "MA17-2")
      (footprint "eagle-import:MA17-2")
      (libsource (lib "eagle-import") (part "MA17-2"))
    )
    (comp (ref "F40")
      (value "MA17-2")
      (footprint "eagle-import:MA17-2")
      (libsource (lib "eagle-import") (part "MA17-2"))
    )
  )
  (nets
    (net (code "1") (name "+15V") (class "Default")
      (node (ref "+V1") (pin "1") (pinfunction "1_1") (pintype "passive"))
      (node (ref "+V2") (pin "1") (pinfunction "1_1") (pintype "passive"))
      (node (ref "+V3") (pin "1") (pinfunction "1_1") (pintype "passive"))
      (node (ref "+V4") (pin "1") (pinfunction "1_1") (pintype "passive"))
      (node (ref "R1") (pin "1") (pinfunction "1_1") (pintype "passive"))
      (node (ref "R10") (pin "1") (pinfunction "1_1") (pintype "passive"))
      (node (ref "R11") (pin "1") (pinfunction "1_1") (pintype "passive"))
      (node (ref "R12") (pin "1") (pinfunction "1_1") (pintype "passive"))
      (node (ref "R13") (pin "1") (pinfunction "1_1") (pintype "passive"))
      (node (ref "R14") (pin "1") (pinfunction "1_1") (pintype "passive"))
      (node (ref "R15") (pin "1") (pinfunction "1_1") (pintype "passive"))
      (node (ref "R16") (pin "1") (pinfunction "1_1") (pintype "passive"))
      (node (ref "R17") (pin "1") (pinfunction "1_1") (pintype "passive"))
      (node (ref "R18") (pin "1") (pinfunction "1_1") (pintype "passive"))
      (node (ref "R19") (pin "1") (pinfunction "1_1") (pintype "passive"))
      (node (ref "R2") (pin "1") (pinfunction "1_1") (pintype "passive"))
      (node (ref "R20") (pin "1") (pinfunction "1_1") (pintype "passive"))
      (node (ref "R21") (pin "1") (pinfunction "1_1") (pintype "passive"))
      (node (ref "R22") (pin "1") (pinfunction "1_1") (pintype "passive"))
      (node (ref "R23") (pin "1") (pinfunction "1_1") (pintype "passive"))
      (node (ref "R24") (pin "1") (pinfunction "1_1") (pintype "passive"))
      (node (ref "R25") (pin "1") (pinfunction "1_1") (pintype "passive"))
      (node (ref "R26") (pin "1") (pinfunction "1_1") (pintype "passive"))
      (node (ref "R27") (pin "1") (pinfunction "1_1") (pintype "passive"))
      (node (ref "R28") (pin "1") (pinfunction "1_1") (pintype "passive"))
      (node (ref "R29") (pin "1") (pinfunction "1_1") (pintype "passive"))
      (node (ref "R3") (pin "1") (pinfunction "1_1") (pintype "passive"))
      (node (ref "R30") (pin "1") (pinfunction "1_1") (pintype "passive"))
      (node (ref "R31") (pin "1") (pinfunction "1_1") (pintype "passive"))
      (node (ref "R32") (pin "1") (pinfunction "1_1") (pintype "passive"))
      (node (ref "R33") (pin "1") (pinfunction "1_1") (pintype "passive"))
      (node (ref "R34") (pin "1") (pinfunction "1_1") (pintype "passive"))
      (node (ref "R35") (pin "1") (pinfunction "1_1") (pintype "passive"))
      (node (ref "R36") (pin "1") (pinfunction "1_1") (pintype "passive"))
      (node (ref "R37") (pin "1") (pinfunction "1_1") (pintype "passive"))
      (node (ref "R38") (pin "1") (pinfunction "1_1") (pintype "passive"))
      (node (ref "R39") (pin "1") (pinfunction "1_1") (pintype "passive"))
      (node (ref "R4") (pin "1") (pinfunction "1_1") (pintype "passive"))
      (node (ref "R40") (pin "1") (pinfunction "1_1") (pintype "passive"))
      (node (ref "R41") (pin "1") (pinfunction "1_1") (pintype "passive"))
      (node (ref "R42") (pin "1") (pinfunction "1_1") (pintype "passive"))
      (node (ref "R43") (pin "1") (pinfunction "1_1") (pintype "passive"))
      (node (ref "R44") (pin "1") (pinfunction "1_1") (pintype "passive"))
      (node (ref "R45") (pin "1") (pinfunction "1_1") (pintype "passive"))
      (node (ref "R46") (pin "1") (pinfunction "1_1") (pintype "passive"))
      (node (ref "R47") (pin "1") (pinfunction "1_1") (pintype "passive"))
      (node (ref "R48") (pin "1") (pinfunction "1_1") (pintype "passive"))
      (node (ref "R49") (pin "1") (pinfunction "1_1") (pintype "passive"))
      (node (ref "R5") (pin "1") (pinfunction "1_1") (pintype "passive"))
      (node (ref "R50") (pin "1") (pinfunction "1_1") (pintype "passive"))
      (node (ref "R51") (pin "1") (pinfunction "1_1") (pintype "passive"))
      (node (ref "R52") (pin "1") (pinfunction "1_1") (pintype "passive"))
      (node (ref "R53") (pin "1") (pinfunction "1_1") (pintype "passive"))
      (node (ref "R54") (pin "1") (pinfunction "1_1") (pintype "passive"))
      (node (ref "R55") (pin "1") (pinfunction "1_1") (pintype "passive"))
      (node (ref "R56") (pin "1") (pinfunction "1_1") (pintype "passive"))
      (node (ref "R57") (pin "1") (pinfunction "1_1") (pintype "passive"))
      (node (ref "R58") (pin "1") (pinfunction "1_1") (pintype "passive"))
      (node (ref "R59") (pin "1") (pinfunction "1_1") (pintype "passive"))
      (node (ref "R6") (pin "1") (pinfunction "1_1") (pintype "passive"))
      (node (ref "R60") (pin "1") (pinfunction "1_1") (pintype "passive"))
      (node (ref "R61") (pin "1") (pinfunction "1_1") (pintype "passive"))
      (node (ref "R62") (pin "1") (pinfunction "1_1") (pintype "passive"))
      (node (ref "R63") (pin "1") (pinfunction "1_1") (pintype "passive"))
      (node (ref "R64") (pin "1") (pinfunction "1_1") (pintype "passive"))
      (node (ref "R65") (pin "1") (pinfunction "1_1") (pintype "passive"))
      (node (ref "R66") (pin "1") (pinfunction "1_1") (pintype "passive"))
      (node (ref "R67") (pin "1") (pinfunction "1_1") (pintype "passive"))
      (node (ref "R68") (pin "1") (pinfunction "1_1") (pintype "passive"))
      (node (ref "R69") (pin "1") (pinfunction "1_1") (pintype "passive"))
      (node (ref "R7") (pin "1") (pinfunction "1_1") (pintype "passive"))
      (node (ref "R70") (pin "1") (pinfunction "1_1") (pintype "passive"))
      (node (ref "R71") (pin "1") (pinfunction "1_1") (pintype "passive"))
      (node (ref "R72") (pin "1") (pinfunction "1_1") (pintype "passive"))
      (node (ref "R73") (pin "1") (pinfunction "1_1") (pintype "passive"))
      (node (ref "R74") (pin "1") (pinfunction "1_1") (pintype "passive"))
      (node (ref "R75") (pin "1") (pinfunction "1_1") (pintype "passive"))
      (node (ref "R76") (pin "1") (pinfunction "1_1") (pintype "passive"))
      (node (ref "R77") (pin "1") (pinfunction "1_1") (pintype "passive"))
      (node (ref "R78") (pin "1") (pinfunction "1_1") (pintype "passive"))
      (node (ref "R79") (pin "1") (pinfunction "1_1") (pintype "passive"))
      (node (ref "R8") (pin "1") (pinfunction "1_1") (pintype "passive"))
      (node (ref "R80") (pin "1") (pinfunction "1_1") (pintype "passive"))
      (node (ref "R81") (pin "1") (pinfunction "1_1") (pintype "passive"))
      (node (ref "R82") (pin "1") (pinfunction "1_1") (pintype "passive"))
      (node (ref "R83") (pin "1") (pinfunction "1_1") (pintype "passive"))
      (node (ref "R84") (pin "1") (pinfunction "1_1") (pintype "passive"))
      (node (ref "R85") (pin "1") (pinfunction "1_1") (pintype "passive"))
      (node (ref "R86") (pin "1") (pinfunction "1_1") (pintype "passive"))
      (node (ref "R87") (pin "1") (pinfunction "1_1") (pintype "passive"))
      (node (ref "R88") (pin "1") (pinfunction "1_1") (pintype "passive"))
      (node (ref "R89") (pin "1") (pinfunction "1_1") (pintype "passive"))
      (node (ref "R9") (pin "1") (pinfunction "1_1") (pintype "passive"))
    )
    (net (code "2") (name "AC0") (class "Default")
      (node (ref "D40TOP") (pin "4") (pinfunction "1_4") (pintype "passive"))
      (node (ref "E40") (pin "7") (pinfunction "7_7") (pintype "passive"))
      (node (ref "T43") (pin "2") (pinfunction "B_2") (pintype "passive"))
    )
    (net (code "3") (name "AC1") (class "Default")
      (node (ref "D40BOT") (pin "2") (pinfunction "1_2") (pintype "passive"))
      (node (ref "E40") (pin "4") (pinfunction "4_4") (pintype "passive"))
      (node (ref "T44") (pin "2") (pinfunction "B_2") (pintype "passive"))
    )
    (net (code "4") (name "AC2") (class "Default")
      (node (ref "D40TOP") (pin "12") (pinfunction "1_12") (pintype "passive"))
      (node (ref "E40") (pin "21") (pinfunction "21_21") (pintype "passive"))
      (node (ref "T45") (pin "2") (pinfunction "B_2") (pintype "passive"))
    )
    (net (code "5") (name "AC3") (class "Default")
      (node (ref "D40BOT") (pin "9") (pinfunction "1_9") (pintype "passive"))
      (node (ref "E40") (pin "14") (pinfunction "14_14") (pintype "passive"))
      (node (ref "T46") (pin "2") (pinfunction "B_2") (pintype "passive"))
    )
    (net (code "6") (name "AC4") (class "Default")
      (node (ref "D40TOP") (pin "17") (pinfunction "1_17") (pintype "passive"))
      (node (ref "E40") (pin "31") (pinfunction "31_31") (pintype "passive"))
      (node (ref "T47") (pin "2") (pinfunction "B_2") (pintype "passive"))
    )
    (net (code "7") (name "AC5") (class "Default")
      (node (ref "D40BOT") (pin "16") (pinfunction "1_16") (pintype "passive"))
      (node (ref "E40") (pin "28") (pinfunction "28_28") (pintype "passive"))
      (node (ref "T48") (pin "2") (pinfunction "B_2") (pintype "passive"))
    )
    (net (code "8") (name "AC6") (class "Default")
      (node (ref "E40TOP") (pin "4") (pinfunction "1_4") (pintype "passive"))
      (node (ref "F40") (pin "7") (pinfunction "7_7") (pintype "passive"))
      (node (ref "T49") (pin "2") (pinfunction "B_2") (pintype "passive"))
    )
    (net (code "9") (name "AC7") (class "Default")
      (node (ref "E40BOT") (pin "2") (pinfunction "1_2") (pintype "passive"))
      (node (ref "F40") (pin "4") (pinfunction "4_4") (pintype "passive"))
      (node (ref "T50") (pin "2") (pinfunction "B_2") (pintype "passive"))
    )
    (net (code "10") (name "AC8") (class "Default")
      (node (ref "E40TOP") (pin "12") (pinfunction "1_12") (pintype "passive"))
      (node (ref "F40") (pin "21") (pinfunction "21_21") (pintype "passive"))
      (node (ref "T51") (pin "2") (pinfunction "B_2") (pintype "passive"))
    )
    (net (code "11") (name "AC9") (class "Default")
      (node (ref "E40BOT") (pin "9") (pinfunction "1_9") (pintype "passive"))
      (node (ref "F40") (pin "14") (pinfunction "14_14") (pintype "passive"))
      (node (ref "T52") (pin "2") (pinfunction "B_2") (pintype "passive"))
    )
    (net (code "12") (name "AC10") (class "Default")
      (node (ref "E40TOP") (pin "17") (pinfunction "1_17") (pintype "passive"))
      (node (ref "F40") (pin "31") (pinfunction "31_31") (pintype "passive"))
      (node (ref "T53") (pin "2") (pinfunction "B_2") (pintype "passive"))
    )
    (net (code "13") (name "AC11") (class "Default")
      (node (ref "E40BOT") (pin "16") (pinfunction "1_16") (pintype "passive"))
      (node (ref "F40") (pin "28") (pinfunction "28_28") (pintype "passive"))
      (node (ref "T54") (pin "2") (pinfunction "B_2") (pintype "passive"))
    )
    (net (code "14") (name "AND") (class "Default")
      (node (ref "D40") (pin "2") (pinfunction "2_2") (pintype "passive"))
      (node (ref "F40BOT") (pin "1") (pinfunction "1_1") (pintype "passive"))
      (node (ref "T82") (pin "2") (pinfunction "B_2") (pintype "passive"))
    )
    (net (code "15") (name "BREAK") (class "Default")
      (node (ref "D40") (pin "22") (pinfunction "22_22") (pintype "passive"))
      (node (ref "F40BOT") (pin "12") (pinfunction "1_12") (pintype "passive"))
      (node (ref "T81") (pin "2") (pinfunction "B_2") (pintype "passive"))
    )
    (net (code "16") (name "CA") (class "Default")
      (node (ref "D40") (pin "32") (pinfunction "32_32") (pintype "passive"))
      (node (ref "F40BOT") (pin "18") (pinfunction "1_18") (pintype "passive"))
      (node (ref "T80") (pin "2") (pinfunction "B_2") (pintype "passive"))
    )
    (net (code "17") (name "DCA") (class "Default")
      (node (ref "D40") (pin "8") (pinfunction "8_8") (pintype "passive"))
      (node (ref "F40BOT") (pin "4") (pinfunction "1_4") (pintype "passive"))
      (node (ref "T85") (pin "2") (pinfunction "B_2") (pintype "passive"))
    )
    (net (code "18") (name "DEFER") (class "Default")
      (node (ref "D40") (pin "26") (pinfunction "26_26") (pintype "passive"))
      (node (ref "F40BOT") (pin "15") (pinfunction "1_15") (pintype "passive"))
      (node (ref "T78") (pin "2") (pinfunction "B_2") (pintype "passive"))
    )
    (net (code "19") (name "DF0") (class "Default")
      (node (ref "C40") (pin "1") (pinfunction "1_1") (pintype "passive"))
      (node (ref "C40TOP") (pin "1") (pinfunction "1_1") (pintype "passive"))
      (node (ref "T1") (pin "2") (pinfunction "B_2") (pintype "passive"))
    )
    (net (code "20") (name "DF1") (class "Default")
      (node (ref "C40") (pin "10") (pinfunction "10_10") (pintype "passive"))
      (node (ref "C40BOT") (pin "5") (pinfunction "1_5") (pintype "passive"))
      (node (ref "T2") (pin "2") (pinfunction "B_2") (pintype "passive"))
    )
    (net (code "21") (name "DF2") (class "Default")
      (node (ref "C40") (pin "11") (pinfunction "11_11") (pintype "passive"))
      (node (ref "C40TOP") (pin "6") (pinfunction "1_6") (pintype "passive"))
      (node (ref "T3") (pin "2") (pinfunction "B_2") (pintype "passive"))
    )
    (net (code "22") (name "EXECUTE") (class "Default")
      (node (ref "D40") (pin "28") (pinfunction "28_28") (pintype "passive"))
      (node (ref "F40BOT") (pin "16") (pinfunction "1_16") (pintype "passive"))
      (node (ref "T77") (pin "2") (pinfunction "B_2") (pintype "passive"))
    )
    (net (code "23") (name "FETCH") (class "Default")
      (node (ref "D40") (pin "24") (pinfunction "24_24") (pintype "passive"))
      (node (ref "F40BOT") (pin "14") (pinfunction "1_14") (pintype "passive"))
      (node (ref "T76") (pin "2") (pinfunction "B_2") (pintype "passive"))
    )
    (net (code "24") (name "GND") (class "Default")
      (node (ref "C40") (pin "17") (pinfunction "17_17") (pintype "passive"))
      (node (ref "C40") (pin "18") (pinfunction "18_18") (pintype "passive"))
      (node (ref "C40") (pin "19") (pinfunction "19_19") (pintype "passive"))
      (node (ref "C40") (pin "20") (pinfunction "20_20") (pintype "passive"))
      (node (ref "C40BOT") (pin "13") (pinfunction "1_13") (pintype "passive"))
      (node (ref "D40") (pin "17") (pinfunction "17_17") (pintype "passive"))
      (node (ref "D40") (pin "18") (pinfunction "18_18") (pintype "passive"))
      (node (ref "D40") (pin "19") (pinfunction "19_19") (pintype "passive"))
      (node (ref "D40") (pin "20") (pinfunction "20_20") (pintype "passive"))
      (node (ref "D40BOT") (pin "13") (pinfunction "1_13") (pintype "passive"))
      (node (ref "E40") (pin "17") (pinfunction "17_17") (pintype "passive"))
      (node (ref "E40") (pin "18") (pinfunction "18_18") (pintype "passive"))
      (node (ref "E40") (pin "19") (pinfunction "19_19") (pintype "passive"))
      (node (ref "E40") (pin "20") (pinfunction "20_20") (pintype "passive"))
      (node (ref "E40BOT") (pin "13") (pinfunction "1_13") (pintype "passive"))
      (node (ref "F40") (pin "17") (pinfunction "17_17") (pintype "passive"))
      (node (ref "F40") (pin "18") (pinfunction "18_18") (pintype "passive"))
      (node (ref "F40") (pin "19") (pinfunction "19_19") (pintype "passive"))
      (node (ref "F40") (pin "20") (pinfunction "20_20") (pintype "passive"))
      (node (ref "F40BOT") (pin "13") (pinfunction "1_13") (pintype "passive"))
      (node (ref "GND1") (pin "1") (pinfunction "1_1") (pintype "passive"))
      (node (ref "GND2") (pin "1") (pinfunction "1_1") (pintype "passive"))
      (node (ref "GND3") (pin "1") (pinfunction "1_1") (pintype "passive"))
      (node (ref "GND4") (pin "1") (pinfunction "1_1") (pintype "passive"))
      (node (ref "T1") (pin "1") (pinfunction "E_1") (pintype "passive"))
      (node (ref "T10") (pin "1") (pinfunction "E_1") (pintype "passive"))
      (node (ref "T11") (pin "1") (pinfunction "E_1") (pintype "passive"))
      (node (ref "T12") (pin "1") (pinfunction "E_1") (pintype "passive"))
      (node (ref "T13") (pin "1") (pinfunction "E_1") (pintype "passive"))
      (node (ref "T14") (pin "1") (pinfunction "E_1") (pintype "passive"))
      (node (ref "T15") (pin "1") (pinfunction "E_1") (pintype "passive"))
      (node (ref "T16") (pin "1") (pinfunction "E_1") (pintype "passive"))
      (node (ref "T17") (pin "1") (pinfunction "E_1") (pintype "passive"))
      (node (ref "T18") (pin "1") (pinfunction "E_1") (pintype "passive"))
      (node (ref "T19") (pin "1") (pinfunction "E_1") (pintype "passive"))
      (node (ref "T2") (pin "1") (pinfunction "E_1") (pintype "passive"))
      (node (ref "T20") (pin "1") (pinfunction "E_1") (pintype "passive"))
      (node (ref "T21") (pin "1") (pinfunction "E_1") (pintype "passive"))
      (node (ref "T22") (pin "1") (pinfunction "E_1") (pintype "passive"))
      (node (ref "T23") (pin "1") (pinfunction "E_1") (pintype "passive"))
      (node (ref "T24") (pin "1") (pinfunction "E_1") (pintype "passive"))
      (node (ref "T25") (pin "1") (pinfunction "E_1") (pintype "passive"))
      (node (ref "T26") (pin "1") (pinfunction "E_1") (pintype "passive"))
      (node (ref "T27") (pin "1") (pinfunction "E_1") (pintype "passive"))
      (node (ref "T28") (pin "1") (pinfunction "E_1") (pintype "passive"))
      (node (ref "T29") (pin "1") (pinfunction "E_1") (pintype "passive"))
      (node (ref "T3") (pin "1") (pinfunction "E_1") (pintype "passive"))
      (node (ref "T30") (pin "1") (pinfunction "E_1") (pintype "passive"))
      (node (ref "T31") (pin "1") (pinfunction "E_1") (pintype "passive"))
      (node (ref "T32") (pin "1") (pinfunction "E_1") (pintype "passive"))
      (node (ref "T33") (pin "1") (pinfunction "E_1") (pintype "passive"))
      (node (ref "T34") (pin "1") (pinfunction "E_1") (pintype "passive"))
      (node (ref "T35") (pin "1") (pinfunction "E_1") (pintype "passive"))
      (node (ref "T36") (pin "1") (pinfunction "E_1") (pintype "passive"))
      (node (ref "T37") (pin "1") (pinfunction "E_1") (pintype "passive"))
      (node (ref "T38") (pin "1") (pinfunction "E_1") (pintype "passive"))
      (node (ref "T39") (pin "1") (pinfunction "E_1") (pintype "passive"))
      (node (ref "T4") (pin "1") (pinfunction "E_1") (pintype "passive"))
      (node (ref "T40") (pin "1") (pinfunction "E_1") (pintype "passive"))
      (node (ref "T41") (pin "1") (pinfunction "E_1") (pintype "passive"))
      (node (ref "T42") (pin "1") (pinfunction "E_1") (pintype "passive"))
      (node (ref "T43") (pin "1") (pinfunction "E_1") (pintype "passive"))
      (node (ref "T44") (pin "1") (pinfunction "E_1") (pintype "passive"))
      (node (ref "T45") (pin "1") (pinfunction "E_1") (pintype "passive"))
      (node (ref "T46") (pin "1") (pinfunction "E_1") (pintype "passive"))
      (node (ref "T47") (pin "1") (pinfunction "E_1") (pintype "passive"))
      (node (ref "T48") (pin "1") (pinfunction "E_1") (pintype "passive"))
      (node (ref "T49") (pin "1") (pinfunction "E_1") (pintype "passive"))
      (node (ref "T5") (pin "1") (pinfunction "E_1") (pintype "passive"))
      (node (ref "T50") (pin "1") (pinfunction "E_1") (pintype "passive"))
      (node (ref "T51") (pin "1") (pinfunction "E_1") (pintype "passive"))
      (node (ref "T52") (pin "1") (pinfunction "E_1") (pintype "passive"))
      (node (ref "T53") (pin "1") (pinfunction "E_1") (pintype "passive"))
      (node (ref "T54") (pin "1") (pinfunction "E_1") (pintype "passive"))
      (node (ref "T55") (pin "1") (pinfunction "E_1") (pintype "passive"))
      (node (ref "T56") (pin "1") (pinfunction "E_1") (pintype "passive"))
      (node (ref "T57") (pin "1") (pinfunction "E_1") (pintype "passive"))
      (node (ref "T58") (pin "1") (pinfunction "E_1") (pintype "passive"))
      (node (ref "T59") (pin "1") (pinfunction "E_1") (pintype "passive"))
      (node (ref "T6") (pin "1") (pinfunction "E_1") (pintype "passive"))
      (node (ref "T60") (pin "1") (pinfunction "E_1") (pintype "passive"))
      (node (ref "T61") (pin "1") (pinfunction "E_1") (pintype "passive"))
      (node (ref "T62") (pin "1") (pinfunction "E_1") (pintype "passive"))
      (node (ref "T63") (pin "1") (pinfunction "E_1") (pintype "passive"))
      (node (ref "T64") (pin "1") (pinfunction "E_1") (pintype "passive"))
      (node (ref "T65") (pin "1") (pinfunction "E_1") (pintype "passive"))
      (node (ref "T66") (pin "1") (pinfunction "E_1") (pintype "passive"))
      (node (ref "T67") (pin "1") (pinfunction "E_1") (pintype "passive"))
      (node (ref "T68") (pin "1") (pinfunction "E_1") (pintype "passive"))
      (node (ref "T69") (pin "1") (pinfunction "E_1") (pintype "passive"))
      (node (ref "T7") (pin "1") (pinfunction "E_1") (pintype "passive"))
      (node (ref "T70") (pin "1") (pinfunction "E_1") (pintype "passive"))
      (node (ref "T71") (pin "1") (pinfunction "E_1") (pintype "passive"))
      (node (ref "T72") (pin "1") (pinfunction "E_1") (pintype "passive"))
      (node (ref "T73") (pin "1") (pinfunction "E_1") (pintype "passive"))
      (node (ref "T74") (pin "1") (pinfunction "E_1") (pintype "passive"))
      (node (ref "T75") (pin "1") (pinfunction "E_1") (pintype "passive"))
      (node (ref "T76") (pin "1") (pinfunction "E_1") (pintype "passive"))
      (node (ref "T77") (pin "1") (pinfunction "E_1") (pintype "passive"))
      (node (ref "T78") (pin "1") (pinfunction "E_1") (pintype "passive"))
      (node (ref "T79") (pin "1") (pinfunction "E_1") (pintype "passive"))
      (node (ref "T8") (pin "1") (pinfunction "E_1") (pintype "passive"))
      (node (ref "T80") (pin "1") (pinfunction "E_1") (pintype "passive"))
      (node (ref "T81") (pin "1") (pinfunction "E_1") (pintype "passive"))
      (node (ref "T82") (pin "1") (pinfunction "E_1") (pintype "passive"))
      (node (ref "T83") (pin "1") (pinfunction "E_1") (pintype "passive"))
      (node (ref "T84") (pin "1") (pinfunction "E_1") (pintype "passive"))
      (node (ref "T85") (pin "1") (pinfunction "E_1") (pintype "passive"))
      (node (ref "T86") (pin "1") (pinfunction "E_1") (pintype "passive"))
      (node (ref "T87") (pin "1") (pinfunction "E_1") (pintype "passive"))
      (node (ref "T88") (pin "1") (pinfunction "E_1") (pintype "passive"))
      (node (ref "T89") (pin "1") (pinfunction "E_1") (pintype "passive"))
      (node (ref "T9") (pin "1") (pinfunction "E_1") (pintype "passive"))
    )
    (net (code "25") (name "IF0") (class "Default")
      (node (ref "C40") (pin "24") (pinfunction "24_24") (pintype "passive"))
      (node (ref "C40BOT") (pin "14") (pinfunction "1_14") (pintype "passive"))
      (node (ref "T4") (pin "2") (pinfunction "B_2") (pintype "passive"))
    )
    (net (code "26") (name "IF1") (class "Default")
      (node (ref "C40") (pin "25") (pinfunction "25_25") (pintype "passive"))
      (node (ref "C40TOP") (pin "14") (pinfunction "1_14") (pintype "passive"))
      (node (ref "T5") (pin "2") (pinfunction "B_2") (pintype "passive"))
    )
    (net (code "27") (name "IF2") (class "Default")
      (node (ref "C40") (pin "34") (pinfunction "34_34") (pintype "passive"))
      (node (ref "C40BOT") (pin "19") (pinfunction "1_19") (pintype "passive"))
      (node (ref "T6") (pin "2") (pinfunction "B_2") (pintype "passive"))
    )
    (net (code "28") (name "ION") (class "Default")
      (node (ref "D40") (pin "34") (pinfunction "34_34") (pintype "passive"))
      (node (ref "F40BOT") (pin "19") (pinfunction "1_19") (pintype "passive"))
      (node (ref "T73") (pin "2") (pinfunction "B_2") (pintype "passive"))
    )
    (net (code "29") (name "IOT") (class "Default")
      (node (ref "D40") (pin "23") (pinfunction "23_23") (pintype "passive"))
      (node (ref "F40TOP") (pin "13") (pinfunction "1_13") (pintype "passive"))
      (node (ref "T88") (pin "2") (pinfunction "B_2") (pintype "passive"))
    )
    (net (code "30") (name "ISZ") (class "Default")
      (node (ref "D40") (pin "6") (pinfunction "6_6") (pintype "passive"))
      (node (ref "F40BOT") (pin "3") (pinfunction "1_3") (pintype "passive"))
      (node (ref "T84") (pin "2") (pinfunction "B_2") (pintype "passive"))
    )
    (net (code "31") (name "JMP") (class "Default")
      (node (ref "D40") (pin "12") (pinfunction "12_12") (pintype "passive"))
      (node (ref "F40BOT") (pin "6") (pinfunction "1_6") (pintype "passive"))
      (node (ref "T87") (pin "2") (pinfunction "B_2") (pintype "passive"))
    )
    (net (code "32") (name "JMS") (class "Default")
      (node (ref "D40") (pin "10") (pinfunction "10_10") (pintype "passive"))
      (node (ref "F40BOT") (pin "5") (pinfunction "1_5") (pintype "passive"))
      (node (ref "T86") (pin "2") (pinfunction "B_2") (pintype "passive"))
    )
    (net (code "33") (name "LINK") (class "Default")
      (node (ref "C40") (pin "28") (pinfunction "28_28") (pintype "passive"))
      (node (ref "C40BOT") (pin "16") (pinfunction "1_16") (pintype "passive"))
      (node (ref "T72") (pin "2") (pinfunction "B_2") (pintype "passive"))
    )
    (net (code "34") (name "MA0") (class "Default")
      (node (ref "D40TOP") (pin "2") (pinfunction "1_2") (pintype "passive"))
      (node (ref "E40") (pin "3") (pinfunction "3_3") (pintype "passive"))
      (node (ref "T19") (pin "2") (pinfunction "B_2") (pintype "passive"))
    )
    (net (code "35") (name "MA1") (class "Default")
      (node (ref "D40BOT") (pin "4") (pinfunction "1_4") (pintype "passive"))
      (node (ref "E40") (pin "8") (pinfunction "8_8") (pintype "passive"))
      (node (ref "T20") (pin "2") (pinfunction "B_2") (pintype "passive"))
    )
    (net (code "36") (name "MA2") (class "Default")
      (node (ref "D40TOP") (pin "7") (pinfunction "1_7") (pintype "passive"))
      (node (ref "E40") (pin "13") (pinfunction "13_13") (pintype "passive"))
      (node (ref "T21") (pin "2") (pinfunction "B_2") (pintype "passive"))
    )
    (net (code "37") (name "MA3") (class "Default")
      (node (ref "D40BOT") (pin "12") (pinfunction "1_12") (pintype "passive"))
      (node (ref "E40") (pin "22") (pinfunction "22_22") (pintype "passive"))
      (node (ref "T22") (pin "2") (pinfunction "B_2") (pintype "passive"))
    )
    (net (code "38") (name "MA4") (class "Default")
      (node (ref "D40TOP") (pin "15") (pinfunction "1_15") (pintype "passive"))
      (node (ref "E40") (pin "27") (pinfunction "27_27") (pintype "passive"))
      (node (ref "T23") (pin "2") (pinfunction "B_2") (pintype "passive"))
    )
    (net (code "39") (name "MA5") (class "Default")
      (node (ref "D40BOT") (pin "18") (pinfunction "1_18") (pintype "passive"))
      (node (ref "E40") (pin "32") (pinfunction "32_32") (pintype "passive"))
      (node (ref "T24") (pin "2") (pinfunction "B_2") (pintype "passive"))
    )
    (net (code "40") (name "MA6") (class "Default")
      (node (ref "E40TOP") (pin "2") (pinfunction "1_2") (pintype "passive"))
      (node (ref "F40") (pin "3") (pinfunction "3_3") (pintype "passive"))
      (node (ref "T25") (pin "2") (pinfunction "B_2") (pintype "passive"))
    )
    (net (code "41") (name "MA7") (class "Default")
      (node (ref "E40BOT") (pin "4") (pinfunction "1_4") (pintype "passive"))
      (node (ref "F40") (pin "8") (pinfunction "8_8") (pintype "passive"))
      (node (ref "T26") (pin "2") (pinfunction "B_2") (pintype "passive"))
    )
    (net (code "42") (name "MA8") (class "Default")
      (node (ref "E40TOP") (pin "7") (pinfunction "1_7") (pintype "passive"))
      (node (ref "F40") (pin "13") (pinfunction "13_13") (pintype "passive"))
      (node (ref "T27") (pin "2") (pinfunction "B_2") (pintype "passive"))
    )
    (net (code "43") (name "MA9") (class "Default")
      (node (ref "E40BOT") (pin "12") (pinfunction "1_12") (pintype "passive"))
      (node (ref "F40") (pin "22") (pinfunction "22_22") (pintype "passive"))
      (node (ref "T28") (pin "2") (pinfunction "B_2") (pintype "passive"))
    )
    (net (code "44") (name "MA10") (class "Default")
      (node (ref "E40TOP") (pin "15") (pinfunction "1_15") (pintype "passive"))
      (node (ref "F40") (pin "27") (pinfunction "27_27") (pintype "passive"))
      (node (ref "T29") (pin "2") (pinfunction "B_2") (pintype "passive"))
    )
    (net (code "45") (name "MA11") (class "Default")
      (node (ref "E40BOT") (pin "18") (pinfunction "1_18") (pintype "passive"))
      (node (ref "F40") (pin "32") (pinfunction "32_32") (pintype "passive"))
      (node (ref "T30") (pin "2") (pinfunction "B_2") (pintype "passive"))
    )
    (net (code "46") (name "MB0") (class "Default")
      (node (ref "D40TOP") (pin "3") (pinfunction "1_3") (pintype "passive"))
      (node (ref "E40") (pin "5") (pinfunction "5_5") (pintype "passive"))
      (node (ref "T31") (pin "2") (pinfunction "B_2") (pintype "passive"))
    )
    (net (code "47") (name "MB1") (class "Default")
      (node (ref "D40BOT") (pin "3") (pinfunction "1_3") (pintype "passive"))
      (node (ref "E40") (pin "6") (pinfunction "6_6") (pintype "passive"))
      (node (ref "T32") (pin "2") (pinfunction "B_2") (pintype "passive"))
    )
    (net (code "48") (name "MB2") (class "Default")
      (node (ref "D40TOP") (pin "8") (pinfunction "1_8") (pintype "passive"))
      (node (ref "E40") (pin "15") (pinfunction "15_15") (pintype "passive"))
      (node (ref "T33") (pin "2") (pinfunction "B_2") (pintype "passive"))
    )
    (net (code "49") (name "MB3") (class "Default")
      (node (ref "D40BOT") (pin "11") (pinfunction "1_11") (pintype "passive"))
      (node (ref "E40") (pin "16") (pinfunction "16_16") (pintype "passive"))
      (node (ref "T34") (pin "2") (pinfunction "B_2") (pintype "passive"))
    )
    (net (code "50") (name "MB4") (class "Default")
      (node (ref "D40TOP") (pin "16") (pinfunction "1_16") (pintype "passive"))
      (node (ref "E40") (pin "29") (pinfunction "29_29") (pintype "passive"))
      (node (ref "T35") (pin "2") (pinfunction "B_2") (pintype "passive"))
    )
    (net (code "51") (name "MB5") (class "Default")
      (node (ref "D40BOT") (pin "17") (pinfunction "1_17") (pintype "passive"))
      (node (ref "E40") (pin "30") (pinfunction "30_30") (pintype "passive"))
      (node (ref "T36") (pin "2") (pinfunction "B_2") (pintype "passive"))
    )
    (net (code "52") (name "MB6") (class "Default")
      (node (ref "E40TOP") (pin "3") (pinfunction "1_3") (pintype "passive"))
      (node (ref "F40") (pin "5") (pinfunction "5_5") (pintype "passive"))
      (node (ref "T37") (pin "2") (pinfunction "B_2") (pintype "passive"))
    )
    (net (code "53") (name "MB7") (class "Default")
      (node (ref "E40BOT") (pin "3") (pinfunction "1_3") (pintype "passive"))
      (node (ref "F40") (pin "6") (pinfunction "6_6") (pintype "passive"))
      (node (ref "T38") (pin "2") (pinfunction "B_2") (pintype "passive"))
    )
    (net (code "54") (name "MB8") (class "Default")
      (node (ref "E40TOP") (pin "8") (pinfunction "1_8") (pintype "passive"))
      (node (ref "F40") (pin "15") (pinfunction "15_15") (pintype "passive"))
      (node (ref "T39") (pin "2") (pinfunction "B_2") (pintype "passive"))
    )
    (net (code "55") (name "MB9") (class "Default")
      (node (ref "E40BOT") (pin "11") (pinfunction "1_11") (pintype "passive"))
      (node (ref "F40") (pin "16") (pinfunction "16_16") (pintype "passive"))
      (node (ref "T40") (pin "2") (pinfunction "B_2") (pintype "passive"))
    )
    (net (code "56") (name "MB10") (class "Default")
      (node (ref "E40TOP") (pin "16") (pinfunction "1_16") (pintype "passive"))
      (node (ref "F40") (pin "29") (pinfunction "29_29") (pintype "passive"))
      (node (ref "T41") (pin "2") (pinfunction "B_2") (pintype "passive"))
    )
    (net (code "57") (name "MB11") (class "Default")
      (node (ref "E40BOT") (pin "17") (pinfunction "1_17") (pintype "passive"))
      (node (ref "F40") (pin "30") (pinfunction "30_30") (pintype "passive"))
      (node (ref "T42") (pin "2") (pinfunction "B_2") (pintype "passive"))
    )
    (net (code "58") (name "MQ0") (class "Default")
      (node (ref "D40TOP") (pin "5") (pinfunction "1_5") (pintype "passive"))
      (node (ref "E40") (pin "9") (pinfunction "9_9") (pintype "passive"))
      (node (ref "T55") (pin "2") (pinfunction "B_2") (pintype "passive"))
    )
    (net (code "59") (name "MQ1") (class "Default")
      (node (ref "D40BOT") (pin "1") (pinfunction "1_1") (pintype "passive"))
      (node (ref "E40") (pin "2") (pinfunction "2_2") (pintype "passive"))
      (node (ref "T56") (pin "2") (pinfunction "B_2") (pintype "passive"))
    )
    (net (code "60") (name "MQ2") (class "Default")
      (node (ref "D40TOP") (pin "13") (pinfunction "1_13") (pintype "passive"))
      (node (ref "E40") (pin "23") (pinfunction "23_23") (pintype "passive"))
      (node (ref "T57") (pin "2") (pinfunction "B_2") (pintype "passive"))
    )
    (net (code "61") (name "MQ3") (class "Default")
      (node (ref "D40BOT") (pin "6") (pinfunction "1_6") (pintype "passive"))
      (node (ref "E40") (pin "12") (pinfunction "12_12") (pintype "passive"))
      (node (ref "T58") (pin "2") (pinfunction "B_2") (pintype "passive"))
    )
    (net (code "62") (name "MQ4") (class "Default")
      (node (ref "D40TOP") (pin "18") (pinfunction "1_18") (pintype "passive"))
      (node (ref "E40") (pin "33") (pinfunction "33_33") (pintype "passive"))
      (node (ref "T59") (pin "2") (pinfunction "B_2") (pintype "passive"))
    )
    (net (code "63") (name "MQ5") (class "Default")
      (node (ref "D40BOT") (pin "15") (pinfunction "1_15") (pintype "passive"))
      (node (ref "E40") (pin "26") (pinfunction "26_26") (pintype "passive"))
      (node (ref "T60") (pin "2") (pinfunction "B_2") (pintype "passive"))
    )
    (net (code "64") (name "MQ6") (class "Default")
      (node (ref "E40TOP") (pin "5") (pinfunction "1_5") (pintype "passive"))
      (node (ref "F40") (pin "9") (pinfunction "9_9") (pintype "passive"))
      (node (ref "T61") (pin "2") (pinfunction "B_2") (pintype "passive"))
    )
    (net (code "65") (name "MQ7") (class "Default")
      (node (ref "E40BOT") (pin "1") (pinfunction "1_1") (pintype "passive"))
      (node (ref "F40") (pin "2") (pinfunction "2_2") (pintype "passive"))
      (node (ref "T62") (pin "2") (pinfunction "B_2") (pintype "passive"))
    )
    (net (code "66") (name "MQ8") (class "Default")
      (node (ref "E40TOP") (pin "13") (pinfunction "1_13") (pintype "passive"))
      (node (ref "F40") (pin "23") (pinfunction "23_23") (pintype "passive"))
      (node (ref "T63") (pin "2") (pinfunction "B_2") (pintype "passive"))
    )
    (net (code "67") (name "MQ9") (class "Default")
      (node (ref "E40BOT") (pin "6") (pinfunction "1_6") (pintype "passive"))
      (node (ref "F40") (pin "12") (pinfunction "12_12") (pintype "passive"))
      (node (ref "T64") (pin "2") (pinfunction "B_2") (pintype "passive"))
    )
    (net (code "68") (name "MQ10") (class "Default")
      (node (ref "E40TOP") (pin "18") (pinfunction "1_18") (pintype "passive"))
      (node (ref "F40") (pin "33") (pinfunction "33_33") (pintype "passive"))
      (node (ref "T65") (pin "2") (pinfunction "B_2") (pintype "passive"))
    )
    (net (code "69") (name "MQ11") (class "Default")
      (node (ref "E40BOT") (pin "15") (pinfunction "1_15") (pintype "passive"))
      (node (ref "F40") (pin "26") (pinfunction "26_26") (pintype "passive"))
      (node (ref "T66") (pin "2") (pinfunction "B_2") (pintype "passive"))
    )
    (net (code "70") (name "Net-(AC0-PadA)") (class "Default")
      (node (ref "AC0") (pin "A") (pinfunction "A_A") (pintype "passive"))
      (node (ref "R43") (pin "2") (pinfunction "2_2") (pintype "passive"))
    )
    (net (code "71") (name "Net-(AC1-PadA)") (class "Default")
      (node (ref "AC1") (pin "A") (pinfunction "A_A") (pintype "passive"))
      (node (ref "R44") (pin "2") (pinfunction "2_2") (pintype "passive"))
    )
    (net (code "72") (name "Net-(AC2-PadA)") (class "Default")
      (node (ref "AC2") (pin "A") (pinfunction "A_A") (pintype "passive"))
      (node (ref "R45") (pin "2") (pinfunction "2_2") (pintype "passive"))
    )
    (net (code "73") (name "Net-(AC3-PadA)") (class "Default")
      (node (ref "AC3") (pin "A") (pinfunction "A_A") (pintype "passive"))
      (node (ref "R46") (pin "2") (pinfunction "2_2") (pintype "passive"))
    )
    (net (code "74") (name "Net-(AC4-PadA)") (class "Default")
      (node (ref "AC4") (pin "A") (pinfunction "A_A") (pintype "passive"))
      (node (ref "R47") (pin "2") (pinfunction "2_2") (pintype "passive"))
    )
    (net (code "75") (name "Net-(AC5-PadA)") (class "Default")
      (node (ref "AC5") (pin "A") (pinfunction "A_A") (pintype "passive"))
      (node (ref "R48") (pin "2") (pinfunction "2_2") (pintype "passive"))
    )
    (net (code "76") (name "Net-(AC6-PadA)") (class "Default")
      (node (ref "AC6") (pin "A") (pinfunction "A_A") (pintype "passive"))
      (node (ref "R49") (pin "2") (pinfunction "2_2") (pintype "passive"))
    )
    (net (code "77") (name "Net-(AC7-PadA)") (class "Default")
      (node (ref "AC7") (pin "A") (pinfunction "A_A") (pintype "passive"))
      (node (ref "R50") (pin "2") (pinfunction "2_2") (pintype "passive"))
    )
    (net (code "78") (name "Net-(AC8-PadA)") (class "Default")
      (node (ref "AC8") (pin "A") (pinfunction "A_A") (pintype "passive"))
      (node (ref "R51") (pin "2") (pinfunction "2_2") (pintype "passive"))
    )
    (net (code "79") (name "Net-(AC9-PadA)") (class "Default")
      (node (ref "AC9") (pin "A") (pinfunction "A_A") (pintype "passive"))
      (node (ref "R52") (pin "2") (pinfunction "2_2") (pintype "passive"))
    )
    (net (code "80") (name "Net-(AC10-PadA)") (class "Default")
      (node (ref "AC10") (pin "A") (pinfunction "A_A") (pintype "passive"))
      (node (ref "R53") (pin "2") (pinfunction "2_2") (pintype "passive"))
    )
    (net (code "81") (name "Net-(AC11-PadA)") (class "Default")
      (node (ref "AC11") (pin "A") (pinfunction "A_A") (pintype "passive"))
      (node (ref "R54") (pin "2") (pinfunction "2_2") (pintype "passive"))
    )
    (net (code "82") (name "Net-(AND-PadA)") (class "Default")
      (node (ref "AND") (pin "A") (pinfunction "A_A") (pintype "passive"))
      (node (ref "R82") (pin "2") (pinfunction "2_2") (pintype "passive"))
    )
    (net (code "83") (name "Net-(BREAK-PadA)") (class "Default")
      (node (ref "BREAK") (pin "A") (pinfunction "A_A") (pintype "passive"))
      (node (ref "R81") (pin "2") (pinfunction "2_2") (pintype "passive"))
    )
    (net (code "84") (name "Net-(CURRENTADDRESS-PadA)") (class "Default")
      (node (ref "CURRENTADDRESS") (pin "A") (pinfunction "A_A") (pintype "passive"))
      (node (ref "R80") (pin "2") (pinfunction "2_2") (pintype "passive"))
    )
    (net (code "85") (name "Net-(DCA-PadA)") (class "Default")
      (node (ref "DCA") (pin "A") (pinfunction "A_A") (pintype "passive"))
      (node (ref "R85") (pin "2") (pinfunction "2_2") (pintype "passive"))
    )
    (net (code "86") (name "Net-(DEFER-PadA)") (class "Default")
      (node (ref "DEFER") (pin "A") (pinfunction "A_A") (pintype "passive"))
      (node (ref "R78") (pin "2") (pinfunction "2_2") (pintype "passive"))
    )
    (net (code "87") (name "Net-(DF0-PadA)") (class "Default")
      (node (ref "DF0") (pin "A") (pinfunction "A_A") (pintype "passive"))
      (node (ref "R1") (pin "2") (pinfunction "2_2") (pintype "passive"))
    )
    (net (code "88") (name "Net-(DF1-PadA)") (class "Default")
      (node (ref "DF1") (pin "A") (pinfunction "A_A") (pintype "passive"))
      (node (ref "R2") (pin "2") (pinfunction "2_2") (pintype "passive"))
    )
    (net (code "89") (name "Net-(DF2-PadA)") (class "Default")
      (node (ref "DF2") (pin "A") (pinfunction "A_A") (pintype "passive"))
      (node (ref "R3") (pin "2") (pinfunction "2_2") (pintype "passive"))
    )
    (net (code "90") (name "Net-(EXECUTE-PadA)") (class "Default")
      (node (ref "EXECUTE") (pin "A") (pinfunction "A_A") (pintype "passive"))
      (node (ref "R77") (pin "2") (pinfunction "2_2") (pintype "passive"))
    )
    (net (code "91") (name "Net-(FETCH-PadA)") (class "Default")
      (node (ref "FETCH") (pin "A") (pinfunction "A_A") (pintype "passive"))
      (node (ref "R76") (pin "2") (pinfunction "2_2") (pintype "passive"))
    )
    (net (code "92") (name "Net-(IF0-PadA)") (class "Default")
      (node (ref "IF0") (pin "A") (pinfunction "A_A") (pintype "passive"))
      (node (ref "R4") (pin "2") (pinfunction "2_2") (pintype "passive"))
    )
    (net (code "93") (name "Net-(IF1-PadA)") (class "Default")
      (node (ref "IF1") (pin "A") (pinfunction "A_A") (pintype "passive"))
      (node (ref "R5") (pin "2") (pinfunction "2_2") (pintype "passive"))
    )
    (net (code "94") (name "Net-(IF2-PadA)") (class "Default")
      (node (ref "IF2") (pin "A") (pinfunction "A_A") (pintype "passive"))
      (node (ref "R6") (pin "2") (pinfunction "2_2") (pintype "passive"))
    )
    (net (code "95") (name "Net-(ION-PadA)") (class "Default")
      (node (ref "ION") (pin "A") (pinfunction "A_A") (pintype "passive"))
      (node (ref "R73") (pin "2") (pinfunction "2_2") (pintype "passive"))
    )
    (net (code "96") (name "Net-(IOT-PadA)") (class "Default")
      (node (ref "IOT") (pin "A") (pinfunction "A_A") (pintype "passive"))
      (node (ref "R88") (pin "2") (pinfunction "2_2") (pintype "passive"))
    )
    (net (code "97") (name "Net-(ISZ-PadA)") (class "Default")
      (node (ref "ISZ") (pin "A") (pinfunction "A_A") (pintype "passive"))
      (node (ref "R84") (pin "2") (pinfunction "2_2") (pintype "passive"))
    )
    (net (code "98") (name "Net-(JMP-PadA)") (class "Default")
      (node (ref "JMP") (pin "A") (pinfunction "A_A") (pintype "passive"))
      (node (ref "R87") (pin "2") (pinfunction "2_2") (pintype "passive"))
    )
    (net (code "99") (name "Net-(JMS-PadA)") (class "Default")
      (node (ref "JMS") (pin "A") (pinfunction "A_A") (pintype "passive"))
      (node (ref "R86") (pin "2") (pinfunction "2_2") (pintype "passive"))
    )
    (net (code "100") (name "Net-(LINK-PadA)") (class "Default")
      (node (ref "LINK") (pin "A") (pinfunction "A_A") (pintype "passive"))
      (node (ref "R72") (pin "2") (pinfunction "2_2") (pintype "passive"))
    )
    (net (code "101") (name "Net-(MA0-PadA)") (class "Default")
      (node (ref "MA0") (pin "A") (pinfunction "A_A") (pintype "passive"))
      (node (ref "R19") (pin "2") (pinfunction "2_2") (pintype "passive"))
    )
    (net (code "102") (name "Net-(MA1-PadA)") (class "Default")
      (node (ref "MA1") (pin "A") (pinfunction "A_A") (pintype "passive"))
      (node (ref "R20") (pin "2") (pinfunction "2_2") (pintype "passive"))
    )
    (net (code "103") (name "Net-(MA2-PadA)") (class "Default")
      (node (ref "MA2") (pin "A") (pinfunction "A_A") (pintype "passive"))
      (node (ref "R21") (pin "2") (pinfunction "2_2") (pintype "passive"))
    )
    (net (code "104") (name "Net-(MA3-PadA)") (class "Default")
      (node (ref "MA3") (pin "A") (pinfunction "A_A") (pintype "passive"))
      (node (ref "R22") (pin "2") (pinfunction "2_2") (pintype "passive"))
    )
    (net (code "105") (name "Net-(MA4-PadA)") (class "Default")
      (node (ref "MA4") (pin "A") (pinfunction "A_A") (pintype "passive"))
      (node (ref "R23") (pin "2") (pinfunction "2_2") (pintype "passive"))
    )
    (net (code "106") (name "Net-(MA5-PadA)") (class "Default")
      (node (ref "MA5") (pin "A") (pinfunction "A_A") (pintype "passive"))
      (node (ref "R24") (pin "2") (pinfunction "2_2") (pintype "passive"))
    )
    (net (code "107") (name "Net-(MA6-PadA)") (class "Default")
      (node (ref "MA6") (pin "A") (pinfunction "A_A") (pintype "passive"))
      (node (ref "R25") (pin "2") (pinfunction "2_2") (pintype "passive"))
    )
    (net (code "108") (name "Net-(MA7-PadA)") (class "Default")
      (node (ref "MA7") (pin "A") (pinfunction "A_A") (pintype "passive"))
      (node (ref "R26") (pin "2") (pinfunction "2_2") (pintype "passive"))
    )
    (net (code "109") (name "Net-(MA8-PadA)") (class "Default")
      (node (ref "MA8") (pin "A") (pinfunction "A_A") (pintype "passive"))
      (node (ref "R27") (pin "2") (pinfunction "2_2") (pintype "passive"))
    )
    (net (code "110") (name "Net-(MA9-PadA)") (class "Default")
      (node (ref "MA9") (pin "A") (pinfunction "A_A") (pintype "passive"))
      (node (ref "R28") (pin "2") (pinfunction "2_2") (pintype "passive"))
    )
    (net (code "111") (name "Net-(MA10-PadA)") (class "Default")
      (node (ref "MA10") (pin "A") (pinfunction "A_A") (pintype "passive"))
      (node (ref "R29") (pin "2") (pinfunction "2_2") (pintype "passive"))
    )
    (net (code "112") (name "Net-(MA11-PadA)") (class "Default")
      (node (ref "MA11") (pin "A") (pinfunction "A_A") (pintype "passive"))
      (node (ref "R30") (pin "2") (pinfunction "2_2") (pintype "passive"))
    )
    (net (code "113") (name "Net-(MB0-PadA)") (class "Default")
      (node (ref "MB0") (pin "A") (pinfunction "A_A") (pintype "passive"))
      (node (ref "R31") (pin "2") (pinfunction "2_2") (pintype "passive"))
    )
    (net (code "114") (name "Net-(MB1-PadA)") (class "Default")
      (node (ref "MB1") (pin "A") (pinfunction "A_A") (pintype "passive"))
      (node (ref "R32") (pin "2") (pinfunction "2_2") (pintype "passive"))
    )
    (net (code "115") (name "Net-(MB2-PadA)") (class "Default")
      (node (ref "MB2") (pin "A") (pinfunction "A_A") (pintype "passive"))
      (node (ref "R33") (pin "2") (pinfunction "2_2") (pintype "passive"))
    )
    (net (code "116") (name "Net-(MB3-PadA)") (class "Default")
      (node (ref "MB3") (pin "A") (pinfunction "A_A") (pintype "passive"))
      (node (ref "R34") (pin "2") (pinfunction "2_2") (pintype "passive"))
    )
    (net (code "117") (name "Net-(MB4-PadA)") (class "Default")
      (node (ref "MB4") (pin "A") (pinfunction "A_A") (pintype "passive"))
      (node (ref "R35") (pin "2") (pinfunction "2_2") (pintype "passive"))
    )
    (net (code "118") (name "Net-(MB5-PadA)") (class "Default")
      (node (ref "MB5") (pin "A") (pinfunction "A_A") (pintype "passive"))
      (node (ref "R36") (pin "2") (pinfunction "2_2") (pintype "passive"))
    )
    (net (code "119") (name "Net-(MB6-PadA)") (class "Default")
      (node (ref "MB6") (pin "A") (pinfunction "A_A") (pintype "passive"))
      (node (ref "R37") (pin "2") (pinfunction "2_2") (pintype "passive"))
    )
    (net (code "120") (name "Net-(MB7-PadA)") (class "Default")
      (node (ref "MB7") (pin "A") (pinfunction "A_A") (pintype "passive"))
      (node (ref "R38") (pin "2") (pinfunction "2_2") (pintype "passive"))
    )
    (net (code "121") (name "Net-(MB8-PadA)") (class "Default")
      (node (ref "MB8") (pin "A") (pinfunction "A_A") (pintype "passive"))
      (node (ref "R39") (pin "2") (pinfunction "2_2") (pintype "passive"))
    )
    (net (code "122") (name "Net-(MB9-PadA)") (class "Default")
      (node (ref "MB9") (pin "A") (pinfunction "A_A") (pintype "passive"))
      (node (ref "R40") (pin "2") (pinfunction "2_2") (pintype "passive"))
    )
    (net (code "123") (name "Net-(MB10-PadA)") (class "Default")
      (node (ref "MB10") (pin "A") (pinfunction "A_A") (pintype "passive"))
      (node (ref "R41") (pin "2") (pinfunction "2_2") (pintype "passive"))
    )
    (net (code "124") (name "Net-(MB11-PadA)") (class "Default")
      (node (ref "MB11") (pin "A") (pinfunction "A_A") (pintype "passive"))
      (node (ref "R42") (pin "2") (pinfunction "2_2") (pintype "passive"))
    )
    (net (code "125") (name "Net-(MQ0-PadA)") (class "Default")
      (node (ref "MQ0") (pin "A") (pinfunction "A_A") (pintype "passive"))
      (node (ref "R55") (pin "2") (pinfunction "2_2") (pintype "passive"))
    )
    (net (code "126") (name "Net-(MQ1-PadA)") (class "Default")
      (node (ref "MQ1") (pin "A") (pinfunction "A_A") (pintype "passive"))
      (node (ref "R56") (pin "2") (pinfunction "2_2") (pintype "passive"))
    )
    (net (code "127") (name "Net-(MQ2-PadA)") (class "Default")
      (node (ref "MQ2") (pin "A") (pinfunction "A_A") (pintype "passive"))
      (node (ref "R57") (pin "2") (pinfunction "2_2") (pintype "passive"))
    )
    (net (code "128") (name "Net-(MQ3-PadA)") (class "Default")
      (node (ref "MQ3") (pin "A") (pinfunction "A_A") (pintype "passive"))
      (node (ref "R58") (pin "2") (pinfunction "2_2") (pintype "passive"))
    )
    (net (code "129") (name "Net-(MQ4-PadA)") (class "Default")
      (node (ref "MQ4") (pin "A") (pinfunction "A_A") (pintype "passive"))
      (node (ref "R59") (pin "2") (pinfunction "2_2") (pintype "passive"))
    )
    (net (code "130") (name "Net-(MQ5-PadA)") (class "Default")
      (node (ref "MQ5") (pin "A") (pinfunction "A_A") (pintype "passive"))
      (node (ref "R60") (pin "2") (pinfunction "2_2") (pintype "passive"))
    )
    (net (code "131") (name "Net-(MQ6-PadA)") (class "Default")
      (node (ref "MQ6") (pin "A") (pinfunction "A_A") (pintype "passive"))
      (node (ref "R61") (pin "2") (pinfunction "2_2") (pintype "passive"))
    )
    (net (code "132") (name "Net-(MQ7-PadA)") (class "Default")
      (node (ref "MQ7") (pin "A") (pinfunction "A_A") (pintype "passive"))
      (node (ref "R62") (pin "2") (pinfunction "2_2") (pintype "passive"))
    )
    (net (code "133") (name "Net-(MQ8-PadA)") (class "Default")
      (node (ref "MQ8") (pin "A") (pinfunction "A_A") (pintype "passive"))
      (node (ref "R63") (pin "2") (pinfunction "2_2") (pintype "passive"))
    )
    (net (code "134") (name "Net-(MQ9-PadA)") (class "Default")
      (node (ref "MQ9") (pin "A") (pinfunction "A_A") (pintype "passive"))
      (node (ref "R64") (pin "2") (pinfunction "2_2") (pintype "passive"))
    )
    (net (code "135") (name "Net-(MQ10-PadA)") (class "Default")
      (node (ref "MQ10") (pin "A") (pinfunction "A_A") (pintype "passive"))
      (node (ref "R65") (pin "2") (pinfunction "2_2") (pintype "passive"))
    )
    (net (code "136") (name "Net-(MQ11-PadA)") (class "Default")
      (node (ref "MQ11") (pin "A") (pinfunction "A_A") (pintype "passive"))
      (node (ref "R66") (pin "2") (pinfunction "2_2") (pintype "passive"))
    )
    (net (code "137") (name "Net-(OPR-PadA)") (class "Default")
      (node (ref "OPR") (pin "A") (pinfunction "A_A") (pintype "passive"))
      (node (ref "R89") (pin "2") (pinfunction "2_2") (pintype "passive"))
    )
    (net (code "138") (name "Net-(PAUSE-PadA)") (class "Default")
      (node (ref "PAUSE") (pin "A") (pinfunction "A_A") (pintype "passive"))
      (node (ref "R74") (pin "2") (pinfunction "2_2") (pintype "passive"))
    )
    (net (code "139") (name "Net-(PC0-PadA)") (class "Default")
      (node (ref "PC0") (pin "A") (pinfunction "A_A") (pintype "passive"))
      (node (ref "R7") (pin "2") (pinfunction "2_2") (pintype "passive"))
    )
    (net (code "140") (name "Net-(PC1-PadA)") (class "Default")
      (node (ref "PC1") (pin "A") (pinfunction "A_A") (pintype "passive"))
      (node (ref "R8") (pin "2") (pinfunction "2_2") (pintype "passive"))
    )
    (net (code "141") (name "Net-(PC2-PadA)") (class "Default")
      (node (ref "PC2") (pin "A") (pinfunction "A_A") (pintype "passive"))
      (node (ref "R9") (pin "2") (pinfunction "2_2") (pintype "passive"))
    )
    (net (code "142") (name "Net-(PC3-PadA)") (class "Default")
      (node (ref "PC3") (pin "A") (pinfunction "A_A") (pintype "passive"))
      (node (ref "R10") (pin "2") (pinfunction "2_2") (pintype "passive"))
    )
    (net (code "143") (name "Net-(PC4-PadA)") (class "Default")
      (node (ref "PC4") (pin "A") (pinfunction "A_A") (pintype "passive"))
      (node (ref "R11") (pin "2") (pinfunction "2_2") (pintype "passive"))
    )
    (net (code "144") (name "Net-(PC5-PadA)") (class "Default")
      (node (ref "PC5") (pin "A") (pinfunction "A_A") (pintype "passive"))
      (node (ref "R12") (pin "2") (pinfunction "2_2") (pintype "passive"))
    )
    (net (code "145") (name "Net-(PC6-PadA)") (class "Default")
      (node (ref "PC6") (pin "A") (pinfunction "A_A") (pintype "passive"))
      (node (ref "R13") (pin "2") (pinfunction "2_2") (pintype "passive"))
    )
    (net (code "146") (name "Net-(PC7-PadA)") (class "Default")
      (node (ref "PC7") (pin "A") (pinfunction "A_A") (pintype "passive"))
      (node (ref "R14") (pin "2") (pinfunction "2_2") (pintype "passive"))
    )
    (net (code "147") (name "Net-(PC8-PadA)") (class "Default")
      (node (ref "PC8") (pin "A") (pinfunction "A_A") (pintype "passive"))
      (node (ref "R15") (pin "2") (pinfunction "2_2") (pintype "passive"))
    )
    (net (code "148") (name "Net-(PC9-PadA)") (class "Default")
      (node (ref "PC9") (pin "A") (pinfunction "A_A") (pintype "passive"))
      (node (ref "R16") (pin "2") (pinfunction "2_2") (pintype "passive"))
    )
    (net (code "149") (name "Net-(PC10-PadA)") (class "Default")
      (node (ref "PC10") (pin "A") (pinfunction "A_A") (pintype "passive"))
      (node (ref "R17") (pin "2") (pinfunction "2_2") (pintype "passive"))
    )
    (net (code "150") (name "Net-(PC11-PadA)") (class "Default")
      (node (ref "PC11") (pin "A") (pinfunction "A_A") (pintype "passive"))
      (node (ref "R18") (pin "2") (pinfunction "2_2") (pintype "passive"))
    )
    (net (code "151") (name "Net-(R67-Pad2)") (class "Default")
      (node (ref "R67") (pin "2") (pinfunction "2_2") (pintype "passive"))
      (node (ref "SC0") (pin "A") (pinfunction "A_A") (pintype "passive"))
    )
    (net (code "152") (name "Net-(R68-Pad2)") (class "Default")
      (node (ref "R68") (pin "2") (pinfunction "2_2") (pintype "passive"))
      (node (ref "SC1") (pin "A") (pinfunction "A_A") (pintype "passive"))
    )
    (net (code "153") (name "Net-(R69-Pad2)") (class "Default")
      (node (ref "R69") (pin "2") (pinfunction "2_2") (pintype "passive"))
      (node (ref "SC2") (pin "A") (pinfunction "A_A") (pintype "passive"))
    )
    (net (code "154") (name "Net-(R70-Pad2)") (class "Default")
      (node (ref "R70") (pin "2") (pinfunction "2_2") (pintype "passive"))
      (node (ref "SC3") (pin "A") (pinfunction "A_A") (pintype "passive"))
    )
    (net (code "155") (name "Net-(R71-Pad2)") (class "Default")
      (node (ref "R71") (pin "2") (pinfunction "2_2") (pintype "passive"))
      (node (ref "SC4") (pin "A") (pinfunction "A_A") (pintype "passive"))
    )
    (net (code "156") (name "Net-(R75-Pad2)") (class "Default")
      (node (ref "R75") (pin "2") (pinfunction "2_2") (pintype "passive"))
      (node (ref "RUN") (pin "A") (pinfunction "A_A") (pintype "passive"))
    )
    (net (code "157") (name "Net-(R79-Pad2)") (class "Default")
      (node (ref "R79") (pin "2") (pinfunction "2_2") (pintype "passive"))
      (node (ref "WORDCOUNT") (pin "A") (pinfunction "A_A") (pintype "passive"))
    )
    (net (code "158") (name "Net-(R83-Pad2)") (class "Default")
      (node (ref "R83") (pin "2") (pinfunction "2_2") (pintype "passive"))
      (node (ref "TAD") (pin "A") (pinfunction "A_A") (pintype "passive"))
    )
    (net (code "159") (name "Net-(T1-C)") (class "Default")
      (node (ref "DF0") (pin "B") (pinfunction "B_B") (pintype "passive"))
      (node (ref "T1") (pin "3") (pinfunction "C_3") (pintype "passive"))
    )
    (net (code "160") (name "Net-(T2-C)") (class "Default")
      (node (ref "DF1") (pin "B") (pinfunction "B_B") (pintype "passive"))
      (node (ref "T2") (pin "3") (pinfunction "C_3") (pintype "passive"))
    )
    (net (code "161") (name "Net-(T3-C)") (class "Default")
      (node (ref "DF2") (pin "B") (pinfunction "B_B") (pintype "passive"))
      (node (ref "T3") (pin "3") (pinfunction "C_3") (pintype "passive"))
    )
    (net (code "162") (name "Net-(T4-C)") (class "Default")
      (node (ref "IF0") (pin "B") (pinfunction "B_B") (pintype "passive"))
      (node (ref "T4") (pin "3") (pinfunction "C_3") (pintype "passive"))
    )
    (net (code "163") (name "Net-(T5-C)") (class "Default")
      (node (ref "IF1") (pin "B") (pinfunction "B_B") (pintype "passive"))
      (node (ref "T5") (pin "3") (pinfunction "C_3") (pintype "passive"))
    )
    (net (code "164") (name "Net-(T6-C)") (class "Default")
      (node (ref "IF2") (pin "B") (pinfunction "B_B") (pintype "passive"))
      (node (ref "T6") (pin "3") (pinfunction "C_3") (pintype "passive"))
    )
    (net (code "165") (name "Net-(T7-C)") (class "Default")
      (node (ref "PC0") (pin "B") (pinfunction "B_B") (pintype "passive"))
      (node (ref "T7") (pin "3") (pinfunction "C_3") (pintype "passive"))
    )
    (net (code "166") (name "Net-(T8-C)") (class "Default")
      (node (ref "PC1") (pin "B") (pinfunction "B_B") (pintype "passive"))
      (node (ref "T8") (pin "3") (pinfunction "C_3") (pintype "passive"))
    )
    (net (code "167") (name "Net-(T9-C)") (class "Default")
      (node (ref "PC2") (pin "B") (pinfunction "B_B") (pintype "passive"))
      (node (ref "T9") (pin "3") (pinfunction "C_3") (pintype "passive"))
    )
    (net (code "168") (name "Net-(T10-C)") (class "Default")
      (node (ref "PC3") (pin "B") (pinfunction "B_B") (pintype "passive"))
      (node (ref "T10") (pin "3") (pinfunction "C_3") (pintype "passive"))
    )
    (net (code "169") (name "Net-(T11-C)") (class "Default")
      (node (ref "PC4") (pin "B") (pinfunction "B_B") (pintype "passive"))
      (node (ref "T11") (pin "3") (pinfunction "C_3") (pintype "passive"))
    )
    (net (code "170") (name "Net-(T12-C)") (class "Default")
      (node (ref "PC5") (pin "B") (pinfunction "B_B") (pintype "passive"))
      (node (ref "T12") (pin "3") (pinfunction "C_3") (pintype "passive"))
    )
    (net (code "171") (name "Net-(T13-C)") (class "Default")
      (node (ref "PC6") (pin "B") (pinfunction "B_B") (pintype "passive"))
      (node (ref "T13") (pin "3") (pinfunction "C_3") (pintype "passive"))
    )
    (net (code "172") (name "Net-(T14-C)") (class "Default")
      (node (ref "PC7") (pin "B") (pinfunction "B_B") (pintype "passive"))
      (node (ref "T14") (pin "3") (pinfunction "C_3") (pintype "passive"))
    )
    (net (code "173") (name "Net-(T15-C)") (class "Default")
      (node (ref "PC8") (pin "B") (pinfunction "B_B") (pintype "passive"))
      (node (ref "T15") (pin "3") (pinfunction "C_3") (pintype "passive"))
    )
    (net (code "174") (name "Net-(T16-C)") (class "Default")
      (node (ref "PC9") (pin "B") (pinfunction "B_B") (pintype "passive"))
      (node (ref "T16") (pin "3") (pinfunction "C_3") (pintype "passive"))
    )
    (net (code "175") (name "Net-(T17-C)") (class "Default")
      (node (ref "PC10") (pin "B") (pinfunction "B_B") (pintype "passive"))
      (node (ref "T17") (pin "3") (pinfunction "C_3") (pintype "passive"))
    )
    (net (code "176") (name "Net-(T18-C)") (class "Default")
      (node (ref "PC11") (pin "B") (pinfunction "B_B") (pintype "passive"))
      (node (ref "T18") (pin "3") (pinfunction "C_3") (pintype "passive"))
    )
    (net (code "177") (name "Net-(T19-C)") (class "Default")
      (node (ref "MA0") (pin "B") (pinfunction "B_B") (pintype "passive"))
      (node (ref "T19") (pin "3") (pinfunction "C_3") (pintype "passive"))
    )
    (net (code "178") (name "Net-(T20-C)") (class "Default")
      (node (ref "MA1") (pin "B") (pinfunction "B_B") (pintype "passive"))
      (node (ref "T20") (pin "3") (pinfunction "C_3") (pintype "passive"))
    )
    (net (code "179") (name "Net-(T21-C)") (class "Default")
      (node (ref "MA2") (pin "B") (pinfunction "B_B") (pintype "passive"))
      (node (ref "T21") (pin "3") (pinfunction "C_3") (pintype "passive"))
    )
    (net (code "180") (name "Net-(T22-C)") (class "Default")
      (node (ref "MA3") (pin "B") (pinfunction "B_B") (pintype "passive"))
      (node (ref "T22") (pin "3") (pinfunction "C_3") (pintype "passive"))
    )
    (net (code "181") (name "Net-(T23-C)") (class "Default")
      (node (ref "MA4") (pin "B") (pinfunction "B_B") (pintype "passive"))
      (node (ref "T23") (pin "3") (pinfunction "C_3") (pintype "passive"))
    )
    (net (code "182") (name "Net-(T24-C)") (class "Default")
      (node (ref "MA5") (pin "B") (pinfunction "B_B") (pintype "passive"))
      (node (ref "T24") (pin "3") (pinfunction "C_3") (pintype "passive"))
    )
    (net (code "183") (name "Net-(T25-C)") (class "Default")
      (node (ref "MA6") (pin "B") (pinfunction "B_B") (pintype "passive"))
      (node (ref "T25") (pin "3") (pinfunction "C_3") (pintype "passive"))
    )
    (net (code "184") (name "Net-(T26-C)") (class "Default")
      (node (ref "MA7") (pin "B") (pinfunction "B_B") (pintype "passive"))
      (node (ref "T26") (pin "3") (pinfunction "C_3") (pintype "passive"))
    )
    (net (code "185") (name "Net-(T27-C)") (class "Default")
      (node (ref "MA8") (pin "B") (pinfunction "B_B") (pintype "passive"))
      (node (ref "T27") (pin "3") (pinfunction "C_3") (pintype "passive"))
    )
    (net (code "186") (name "Net-(T28-C)") (class "Default")
      (node (ref "MA9") (pin "B") (pinfunction "B_B") (pintype "passive"))
      (node (ref "T28") (pin "3") (pinfunction "C_3") (pintype "passive"))
    )
    (net (code "187") (name "Net-(T29-C)") (class "Default")
      (node (ref "MA10") (pin "B") (pinfunction "B_B") (pintype "passive"))
      (node (ref "T29") (pin "3") (pinfunction "C_3") (pintype "passive"))
    )
    (net (code "188") (name "Net-(T30-C)") (class "Default")
      (node (ref "MA11") (pin "B") (pinfunction "B_B") (pintype "passive"))
      (node (ref "T30") (pin "3") (pinfunction "C_3") (pintype "passive"))
    )
    (net (code "189") (name "Net-(T31-C)") (class "Default")
      (node (ref "MB0") (pin "B") (pinfunction "B_B") (pintype "passive"))
      (node (ref "T31") (pin "3") (pinfunction "C_3") (pintype "passive"))
    )
    (net (code "190") (name "Net-(T32-C)") (class "Default")
      (node (ref "MB1") (pin "B") (pinfunction "B_B") (pintype "passive"))
      (node (ref "T32") (pin "3") (pinfunction "C_3") (pintype "passive"))
    )
    (net (code "191") (name "Net-(T33-C)") (class "Default")
      (node (ref "MB2") (pin "B") (pinfunction "B_B") (pintype "passive"))
      (node (ref "T33") (pin "3") (pinfunction "C_3") (pintype "passive"))
    )
    (net (code "192") (name "Net-(T34-C)") (class "Default")
      (node (ref "MB3") (pin "B") (pinfunction "B_B") (pintype "passive"))
      (node (ref "T34") (pin "3") (pinfunction "C_3") (pintype "passive"))
    )
    (net (code "193") (name "Net-(T35-C)") (class "Default")
      (node (ref "MB4") (pin "B") (pinfunction "B_B") (pintype "passive"))
      (node (ref "T35") (pin "3") (pinfunction "C_3") (pintype "passive"))
    )
    (net (code "194") (name "Net-(T36-C)") (class "Default")
      (node (ref "MB5") (pin "B") (pinfunction "B_B") (pintype "passive"))
      (node (ref "T36") (pin "3") (pinfunction "C_3") (pintype "passive"))
    )
    (net (code "195") (name "Net-(T37-C)") (class "Default")
      (node (ref "MB6") (pin "B") (pinfunction "B_B") (pintype "passive"))
      (node (ref "T37") (pin "3") (pinfunction "C_3") (pintype "passive"))
    )
    (net (code "196") (name "Net-(T38-C)") (class "Default")
      (node (ref "MB7") (pin "B") (pinfunction "B_B") (pintype "passive"))
      (node (ref "T38") (pin "3") (pinfunction "C_3") (pintype "passive"))
    )
    (net (code "197") (name "Net-(T39-C)") (class "Default")
      (node (ref "MB8") (pin "B") (pinfunction "B_B") (pintype "passive"))
      (node (ref "T39") (pin "3") (pinfunction "C_3") (pintype "passive"))
    )
    (net (code "198") (name "Net-(T40-C)") (class "Default")
      (node (ref "MB9") (pin "B") (pinfunction "B_B") (pintype "passive"))
      (node (ref "T40") (pin "3") (pinfunction "C_3") (pintype "passive"))
    )
    (net (code "199") (name "Net-(T41-C)") (class "Default")
      (node (ref "MB10") (pin "B") (pinfunction "B_B") (pintype "passive"))
      (node (ref "T41") (pin "3") (pinfunction "C_3") (pintype "passive"))
    )
    (net (code "200") (name "Net-(T42-C)") (class "Default")
      (node (ref "MB11") (pin "B") (pinfunction "B_B") (pintype "passive"))
      (node (ref "T42") (pin "3") (pinfunction "C_3") (pintype "passive"))
    )
    (net (code "201") (name "Net-(T43-C)") (class "Default")
      (node (ref "AC0") (pin "B") (pinfunction "B_B") (pintype "passive"))
      (node (ref "T43") (pin "3") (pinfunction "C_3") (pintype "passive"))
    )
    (net (code "202") (name "Net-(T44-C)") (class "Default")
      (node (ref "AC1") (pin "B") (pinfunction "B_B") (pintype "passive"))
      (node (ref "T44") (pin "3") (pinfunction "C_3") (pintype "passive"))
    )
    (net (code "203") (name "Net-(T45-C)") (class "Default")
      (node (ref "AC2") (pin "B") (pinfunction "B_B") (pintype "passive"))
      (node (ref "T45") (pin "3") (pinfunction "C_3") (pintype "passive"))
    )
    (net (code "204") (name "Net-(T46-C)") (class "Default")
      (node (ref "AC3") (pin "B") (pinfunction "B_B") (pintype "passive"))
      (node (ref "T46") (pin "3") (pinfunction "C_3") (pintype "passive"))
    )
    (net (code "205") (name "Net-(T47-C)") (class "Default")
      (node (ref "AC4") (pin "B") (pinfunction "B_B") (pintype "passive"))
      (node (ref "T47") (pin "3") (pinfunction "C_3") (pintype "passive"))
    )
    (net (code "206") (name "Net-(T48-C)") (class "Default")
      (node (ref "AC5") (pin "B") (pinfunction "B_B") (pintype "passive"))
      (node (ref "T48") (pin "3") (pinfunction "C_3") (pintype "passive"))
    )
    (net (code "207") (name "Net-(T49-C)") (class "Default")
      (node (ref "AC6") (pin "B") (pinfunction "B_B") (pintype "passive"))
      (node (ref "T49") (pin "3") (pinfunction "C_3") (pintype "passive"))
    )
    (net (code "208") (name "Net-(T50-C)") (class "Default")
      (node (ref "AC7") (pin "B") (pinfunction "B_B") (pintype "passive"))
      (node (ref "T50") (pin "3") (pinfunction "C_3") (pintype "passive"))
    )
    (net (code "209") (name "Net-(T51-C)") (class "Default")
      (node (ref "AC8") (pin "B") (pinfunction "B_B") (pintype "passive"))
      (node (ref "T51") (pin "3") (pinfunction "C_3") (pintype "passive"))
    )
    (net (code "210") (name "Net-(T52-C)") (class "Default")
      (node (ref "AC9") (pin "B") (pinfunction "B_B") (pintype "passive"))
      (node (ref "T52") (pin "3") (pinfunction "C_3") (pintype "passive"))
    )
    (net (code "211") (name "Net-(T53-C)") (class "Default")
      (node (ref "AC10") (pin "B") (pinfunction "B_B") (pintype "passive"))
      (node (ref "T53") (pin "3") (pinfunction "C_3") (pintype "passive"))
    )
    (net (code "212") (name "Net-(T54-C)") (class "Default")
      (node (ref "AC11") (pin "B") (pinfunction "B_B") (pintype "passive"))
      (node (ref "T54") (pin "3") (pinfunction "C_3") (pintype "passive"))
    )
    (net (code "213") (name "Net-(T55-C)") (class "Default")
      (node (ref "MQ0") (pin "B") (pinfunction "B_B") (pintype "passive"))
      (node (ref "T55") (pin "3") (pinfunction "C_3") (pintype "passive"))
    )
    (net (code "214") (name "Net-(T56-C)") (class "Default")
      (node (ref "MQ1") (pin "B") (pinfunction "B_B") (pintype "passive"))
      (node (ref "T56") (pin "3") (pinfunction "C_3") (pintype "passive"))
    )
    (net (code "215") (name "Net-(T57-C)") (class "Default")
      (node (ref "MQ2") (pin "B") (pinfunction "B_B") (pintype "passive"))
      (node (ref "T57") (pin "3") (pinfunction "C_3") (pintype "passive"))
    )
    (net (code "216") (name "Net-(T58-C)") (class "Default")
      (node (ref "MQ3") (pin "B") (pinfunction "B_B") (pintype "passive"))
      (node (ref "T58") (pin "3") (pinfunction "C_3") (pintype "passive"))
    )
    (net (code "217") (name "Net-(T59-C)") (class "Default")
      (node (ref "MQ4") (pin "B") (pinfunction "B_B") (pintype "passive"))
      (node (ref "T59") (pin "3") (pinfunction "C_3") (pintype "passive"))
    )
    (net (code "218") (name "Net-(T60-C)") (class "Default")
      (node (ref "MQ5") (pin "B") (pinfunction "B_B") (pintype "passive"))
      (node (ref "T60") (pin "3") (pinfunction "C_3") (pintype "passive"))
    )
    (net (code "219") (name "Net-(T61-C)") (class "Default")
      (node (ref "MQ6") (pin "B") (pinfunction "B_B") (pintype "passive"))
      (node (ref "T61") (pin "3") (pinfunction "C_3") (pintype "passive"))
    )
    (net (code "220") (name "Net-(T62-C)") (class "Default")
      (node (ref "MQ7") (pin "B") (pinfunction "B_B") (pintype "passive"))
      (node (ref "T62") (pin "3") (pinfunction "C_3") (pintype "passive"))
    )
    (net (code "221") (name "Net-(T63-C)") (class "Default")
      (node (ref "MQ8") (pin "B") (pinfunction "B_B") (pintype "passive"))
      (node (ref "T63") (pin "3") (pinfunction "C_3") (pintype "passive"))
    )
    (net (code "222") (name "Net-(T64-C)") (class "Default")
      (node (ref "MQ9") (pin "B") (pinfunction "B_B") (pintype "passive"))
      (node (ref "T64") (pin "3") (pinfunction "C_3") (pintype "passive"))
    )
    (net (code "223") (name "Net-(T65-C)") (class "Default")
      (node (ref "MQ10") (pin "B") (pinfunction "B_B") (pintype "passive"))
      (node (ref "T65") (pin "3") (pinfunction "C_3") (pintype "passive"))
    )
    (net (code "224") (name "Net-(T66-C)") (class "Default")
      (node (ref "MQ11") (pin "B") (pinfunction "B_B") (pintype "passive"))
      (node (ref "T66") (pin "3") (pinfunction "C_3") (pintype "passive"))
    )
    (net (code "225") (name "Net-(T67-C)") (class "Default")
      (node (ref "SC0") (pin "B") (pinfunction "B_B") (pintype "passive"))
      (node (ref "T67") (pin "3") (pinfunction "C_3") (pintype "passive"))
    )
    (net (code "226") (name "Net-(T68-C)") (class "Default")
      (node (ref "SC1") (pin "B") (pinfunction "B_B") (pintype "passive"))
      (node (ref "T68") (pin "3") (pinfunction "C_3") (pintype "passive"))
    )
    (net (code "227") (name "Net-(T69-C)") (class "Default")
      (node (ref "SC2") (pin "B") (pinfunction "B_B") (pintype "passive"))
      (node (ref "T69") (pin "3") (pinfunction "C_3") (pintype "passive"))
    )
    (net (code "228") (name "Net-(T70-C)") (class "Default")
      (node (ref "SC3") (pin "B") (pinfunction "B_B") (pintype "passive"))
      (node (ref "T70") (pin "3") (pinfunction "C_3") (pintype "passive"))
    )
    (net (code "229") (name "Net-(T71-C)") (class "Default")
      (node (ref "SC4") (pin "B") (pinfunction "B_B") (pintype "passive"))
      (node (ref "T71") (pin "3") (pinfunction "C_3") (pintype "passive"))
    )
    (net (code "230") (name "Net-(T72-C)") (class "Default")
      (node (ref "LINK") (pin "B") (pinfunction "B_B") (pintype "passive"))
      (node (ref "T72") (pin "3") (pinfunction "C_3") (pintype "passive"))
    )
    (net (code "231") (name "Net-(T73-C)") (class "Default")
      (node (ref "ION") (pin "B") (pinfunction "B_B") (pintype "passive"))
      (node (ref "T73") (pin "3") (pinfunction "C_3") (pintype "passive"))
    )
    (net (code "232") (name "Net-(T74-C)") (class "Default")
      (node (ref "PAUSE") (pin "B") (pinfunction "B_B") (pintype "passive"))
      (node (ref "T74") (pin "3") (pinfunction "C_3") (pintype "passive"))
    )
    (net (code "233") (name "Net-(T75-C)") (class "Default")
      (node (ref "RUN") (pin "B") (pinfunction "B_B") (pintype "passive"))
      (node (ref "T75") (pin "3") (pinfunction "C_3") (pintype "passive"))
    )
    (net (code "234") (name "Net-(T76-C)") (class "Default")
      (node (ref "FETCH") (pin "B") (pinfunction "B_B") (pintype "passive"))
      (node (ref "T76") (pin "3") (pinfunction "C_3") (pintype "passive"))
    )
    (net (code "235") (name "Net-(T77-C)") (class "Default")
      (node (ref "EXECUTE") (pin "B") (pinfunction "B_B") (pintype "passive"))
      (node (ref "T77") (pin "3") (pinfunction "C_3") (pintype "passive"))
    )
    (net (code "236") (name "Net-(T78-C)") (class "Default")
      (node (ref "DEFER") (pin "B") (pinfunction "B_B") (pintype "passive"))
      (node (ref "T78") (pin "3") (pinfunction "C_3") (pintype "passive"))
    )
    (net (code "237") (name "Net-(T79-C)") (class "Default")
      (node (ref "T79") (pin "3") (pinfunction "C_3") (pintype "passive"))
      (node (ref "WORDCOUNT") (pin "B") (pinfunction "B_B") (pintype "passive"))
    )
    (net (code "238") (name "Net-(T80-C)") (class "Default")
      (node (ref "CURRENTADDRESS") (pin "B") (pinfunction "B_B") (pintype "passive"))
      (node (ref "T80") (pin "3") (pinfunction "C_3") (pintype "passive"))
    )
    (net (code "239") (name "Net-(T81-C)") (class "Default")
      (node (ref "BREAK") (pin "B") (pinfunction "B_B") (pintype "passive"))
      (node (ref "T81") (pin "3") (pinfunction "C_3") (pintype "passive"))
    )
    (net (code "240") (name "Net-(T82-C)") (class "Default")
      (node (ref "AND") (pin "B") (pinfunction "B_B") (pintype "passive"))
      (node (ref "T82") (pin "3") (pinfunction "C_3") (pintype "passive"))
    )
    (net (code "241") (name "Net-(T83-C)") (class "Default")
      (node (ref "T83") (pin "3") (pinfunction "C_3") (pintype "passive"))
      (node (ref "TAD") (pin "B") (pinfunction "B_B") (pintype "passive"))
    )
    (net (code "242") (name "Net-(T84-C)") (class "Default")
      (node (ref "ISZ") (pin "B") (pinfunction "B_B") (pintype "passive"))
      (node (ref "T84") (pin "3") (pinfunction "C_3") (pintype "passive"))
    )
    (net (code "243") (name "Net-(T85-C)") (class "Default")
      (node (ref "DCA") (pin "B") (pinfunction "B_B") (pintype "passive"))
      (node (ref "T85") (pin "3") (pinfunction "C_3") (pintype "passive"))
    )
    (net (code "244") (name "Net-(T86-C)") (class "Default")
      (node (ref "JMS") (pin "B") (pinfunction "B_B") (pintype "passive"))
      (node (ref "T86") (pin "3") (pinfunction "C_3") (pintype "passive"))
    )
    (net (code "245") (name "Net-(T87-C)") (class "Default")
      (node (ref "JMP") (pin "B") (pinfunction "B_B") (pintype "passive"))
      (node (ref "T87") (pin "3") (pinfunction "C_3") (pintype "passive"))
    )
    (net (code "246") (name "Net-(T88-C)") (class "Default")
      (node (ref "IOT") (pin "B") (pinfunction "B_B") (pintype "passive"))
      (node (ref "T88") (pin "3") (pinfunction "C_3") (pintype "passive"))
    )
    (net (code "247") (name "Net-(T89-C)") (class "Default")
      (node (ref "OPR") (pin "B") (pinfunction "B_B") (pintype "passive"))
      (node (ref "T89") (pin "3") (pinfunction "C_3") (pintype "passive"))
    )
    (net (code "248") (name "OPR") (class "Default")
      (node (ref "D40") (pin "16") (pinfunction "16_16") (pintype "passive"))
      (node (ref "F40BOT") (pin "11") (pinfunction "1_11") (pintype "passive"))
      (node (ref "T89") (pin "2") (pinfunction "B_2") (pintype "passive"))
    )
    (net (code "249") (name "PAUSE") (class "Default")
      (node (ref "D40") (pin "31") (pinfunction "31_31") (pintype "passive"))
      (node (ref "F40TOP") (pin "17") (pinfunction "1_17") (pintype "passive"))
      (node (ref "T74") (pin "2") (pinfunction "B_2") (pintype "passive"))
    )
    (net (code "250") (name "PC0") (class "Default")
      (node (ref "D40TOP") (pin "1") (pinfunction "1_1") (pintype "passive"))
      (node (ref "E40") (pin "1") (pinfunction "1_1") (pintype "passive"))
      (node (ref "T7") (pin "2") (pinfunction "B_2") (pintype "passive"))
    )
    (net (code "251") (name "PC1") (class "Default")
      (node (ref "D40BOT") (pin "5") (pinfunction "1_5") (pintype "passive"))
      (node (ref "E40") (pin "10") (pinfunction "10_10") (pintype "passive"))
      (node (ref "T8") (pin "2") (pinfunction "B_2") (pintype "passive"))
    )
    (net (code "252") (name "PC2") (class "Default")
      (node (ref "D40TOP") (pin "6") (pinfunction "1_6") (pintype "passive"))
      (node (ref "E40") (pin "11") (pinfunction "11_11") (pintype "passive"))
      (node (ref "T9") (pin "2") (pinfunction "B_2") (pintype "passive"))
    )
    (net (code "253") (name "PC3") (class "Default")
      (node (ref "D40BOT") (pin "14") (pinfunction "1_14") (pintype "passive"))
      (node (ref "E40") (pin "24") (pinfunction "24_24") (pintype "passive"))
      (node (ref "T10") (pin "2") (pinfunction "B_2") (pintype "passive"))
    )
    (net (code "254") (name "PC4") (class "Default")
      (node (ref "D40TOP") (pin "14") (pinfunction "1_14") (pintype "passive"))
      (node (ref "E40") (pin "25") (pinfunction "25_25") (pintype "passive"))
      (node (ref "T11") (pin "2") (pinfunction "B_2") (pintype "passive"))
    )
    (net (code "255") (name "PC5") (class "Default")
      (node (ref "D40BOT") (pin "19") (pinfunction "1_19") (pintype "passive"))
      (node (ref "E40") (pin "34") (pinfunction "34_34") (pintype "passive"))
      (node (ref "T12") (pin "2") (pinfunction "B_2") (pintype "passive"))
    )
    (net (code "256") (name "PC6") (class "Default")
      (node (ref "E40TOP") (pin "1") (pinfunction "1_1") (pintype "passive"))
      (node (ref "F40") (pin "1") (pinfunction "1_1") (pintype "passive"))
      (node (ref "T13") (pin "2") (pinfunction "B_2") (pintype "passive"))
    )
    (net (code "257") (name "PC7") (class "Default")
      (node (ref "E40BOT") (pin "5") (pinfunction "1_5") (pintype "passive"))
      (node (ref "F40") (pin "10") (pinfunction "10_10") (pintype "passive"))
      (node (ref "T14") (pin "2") (pinfunction "B_2") (pintype "passive"))
    )
    (net (code "258") (name "PC8") (class "Default")
      (node (ref "E40TOP") (pin "6") (pinfunction "1_6") (pintype "passive"))
      (node (ref "F40") (pin "11") (pinfunction "11_11") (pintype "passive"))
      (node (ref "T15") (pin "2") (pinfunction "B_2") (pintype "passive"))
    )
    (net (code "259") (name "PC9") (class "Default")
      (node (ref "E40BOT") (pin "14") (pinfunction "1_14") (pintype "passive"))
      (node (ref "F40") (pin "24") (pinfunction "24_24") (pintype "passive"))
      (node (ref "T16") (pin "2") (pinfunction "B_2") (pintype "passive"))
    )
    (net (code "260") (name "PC10") (class "Default")
      (node (ref "E40TOP") (pin "14") (pinfunction "1_14") (pintype "passive"))
      (node (ref "F40") (pin "25") (pinfunction "25_25") (pintype "passive"))
      (node (ref "T17") (pin "2") (pinfunction "B_2") (pintype "passive"))
    )
    (net (code "261") (name "PC11") (class "Default")
      (node (ref "E40BOT") (pin "19") (pinfunction "1_19") (pintype "passive"))
      (node (ref "F40") (pin "34") (pinfunction "34_34") (pintype "passive"))
      (node (ref "T18") (pin "2") (pinfunction "B_2") (pintype "passive"))
    )
    (net (code "262") (name "RUN") (class "Default")
      (node (ref "D40") (pin "33") (pinfunction "33_33") (pintype "passive"))
      (node (ref "F40TOP") (pin "18") (pinfunction "1_18") (pintype "passive"))
      (node (ref "T75") (pin "2") (pinfunction "B_2") (pintype "passive"))
    )
    (net (code "263") (name "SC0") (class "Default")
      (node (ref "C40") (pin "9") (pinfunction "9_9") (pintype "passive"))
      (node (ref "C40TOP") (pin "5") (pinfunction "1_5") (pintype "passive"))
      (node (ref "T67") (pin "2") (pinfunction "B_2") (pintype "passive"))
    )
    (net (code "264") (name "SC1") (class "Default")
      (node (ref "C40") (pin "2") (pinfunction "2_2") (pintype "passive"))
      (node (ref "C40BOT") (pin "1") (pinfunction "1_1") (pintype "passive"))
      (node (ref "T68") (pin "2") (pinfunction "B_2") (pintype "passive"))
    )
    (net (code "265") (name "SC2") (class "Default")
      (node (ref "C40") (pin "23") (pinfunction "23_23") (pintype "passive"))
      (node (ref "C40TOP") (pin "13") (pinfunction "1_13") (pintype "passive"))
      (node (ref "T69") (pin "2") (pinfunction "B_2") (pintype "passive"))
    )
    (net (code "266") (name "SC3") (class "Default")
      (node (ref "C40") (pin "12") (pinfunction "12_12") (pintype "passive"))
      (node (ref "C40BOT") (pin "6") (pinfunction "1_6") (pintype "passive"))
      (node (ref "T70") (pin "2") (pinfunction "B_2") (pintype "passive"))
    )
    (net (code "267") (name "SC4") (class "Default")
      (node (ref "C40") (pin "33") (pinfunction "33_33") (pintype "passive"))
      (node (ref "C40TOP") (pin "18") (pinfunction "1_18") (pintype "passive"))
      (node (ref "T71") (pin "2") (pinfunction "B_2") (pintype "passive"))
    )
    (net (code "268") (name "TAD") (class "Default")
      (node (ref "D40") (pin "4") (pinfunction "4_4") (pintype "passive"))
      (node (ref "F40BOT") (pin "2") (pinfunction "1_2") (pintype "passive"))
      (node (ref "T83") (pin "2") (pinfunction "B_2") (pintype "passive"))
    )
    (net (code "269") (name "WC") (class "Default")
      (node (ref "D40") (pin "30") (pinfunction "30_30") (pintype "passive"))
      (node (ref "F40BOT") (pin "17") (pinfunction "1_17") (pintype "passive"))
      (node (ref "T79") (pin "2") (pinfunction "B_2") (pintype "passive"))
    )
    (net (code "270") (name "unconnected-(C40-Pad3)") (class "Default")
      (node (ref "C40") (pin "3") (pinfunction "3_3") (pintype "passive"))
    )
    (net (code "271") (name "unconnected-(C40-Pad4)") (class "Default")
      (node (ref "C40") (pin "4") (pinfunction "4_4") (pintype "passive"))
    )
    (net (code "272") (name "unconnected-(C40-Pad5)") (class "Default")
      (node (ref "C40") (pin "5") (pinfunction "5_5") (pintype "passive"))
    )
    (net (code "273") (name "unconnected-(C40-Pad6)") (class "Default")
      (node (ref "C40") (pin "6") (pinfunction "6_6") (pintype "passive"))
    )
    (net (code "274") (name "unconnected-(C40-Pad7)") (class "Default")
      (node (ref "C40") (pin "7") (pinfunction "7_7") (pintype "passive"))
    )
    (net (code "275") (name "unconnected-(C40-Pad8)") (class "Default")
      (node (ref "C40") (pin "8") (pinfunction "8_8") (pintype "passive"))
    )
    (net (code "276") (name "unconnected-(C40-Pad13)") (class "Default")
      (node (ref "C40") (pin "13") (pinfunction "13_13") (pintype "passive"))
    )
    (net (code "277") (name "unconnected-(C40-Pad14)") (class "Default")
      (node (ref "C40") (pin "14") (pinfunction "14_14") (pintype "passive"))
    )
    (net (code "278") (name "unconnected-(C40-Pad15)") (class "Default")
      (node (ref "C40") (pin "15") (pinfunction "15_15") (pintype "passive"))
    )
    (net (code "279") (name "unconnected-(C40-Pad16)") (class "Default")
      (node (ref "C40") (pin "16") (pinfunction "16_16") (pintype "passive"))
    )
    (net (code "280") (name "unconnected-(C40-Pad21)") (class "Default")
      (node (ref "C40") (pin "21") (pinfunction "21_21") (pintype "passive"))
    )
    (net (code "281") (name "unconnected-(C40-Pad22)") (class "Default")
      (node (ref "C40") (pin "22") (pinfunction "22_22") (pintype "passive"))
    )
    (net (code "282") (name "unconnected-(C40-Pad26)") (class "Default")
      (node (ref "C40") (pin "26") (pinfunction "26_26") (pintype "passive"))
    )
    (net (code "283") (name "unconnected-(C40-Pad27)") (class "Default")
      (node (ref "C40") (pin "27") (pinfunction "27_27") (pintype "passive"))
    )
    (net (code "284") (name "unconnected-(C40-Pad29)") (class "Default")
      (node (ref "C40") (pin "29") (pinfunction "29_29") (pintype "passive"))
    )
    (net (code "285") (name "unconnected-(C40-Pad30)") (class "Default")
      (node (ref "C40") (pin "30") (pinfunction "30_30") (pintype "passive"))
    )
    (net (code "286") (name "unconnected-(C40-Pad31)") (class "Default")
      (node (ref "C40") (pin "31") (pinfunction "31_31") (pintype "passive"))
    )
    (net (code "287") (name "unconnected-(C40-Pad32)") (class "Default")
      (node (ref "C40") (pin "32") (pinfunction "32_32") (pintype "passive"))
    )
    (net (code "288") (name "unconnected-(D40-Pad1)") (class "Default")
      (node (ref "D40") (pin "1") (pinfunction "1_1") (pintype "passive"))
    )
    (net (code "289") (name "unconnected-(D40-Pad3)") (class "Default")
      (node (ref "D40") (pin "3") (pinfunction "3_3") (pintype "passive"))
    )
    (net (code "290") (name "unconnected-(D40-Pad5)") (class "Default")
      (node (ref "D40") (pin "5") (pinfunction "5_5") (pintype "passive"))
    )
    (net (code "291") (name "unconnected-(D40-Pad7)") (class "Default")
      (node (ref "D40") (pin "7") (pinfunction "7_7") (pintype "passive"))
    )
    (net (code "292") (name "unconnected-(D40-Pad9)") (class "Default")
      (node (ref "D40") (pin "9") (pinfunction "9_9") (pintype "passive"))
    )
    (net (code "293") (name "unconnected-(D40-Pad11)") (class "Default")
      (node (ref "D40") (pin "11") (pinfunction "11_11") (pintype "passive"))
    )
    (net (code "294") (name "unconnected-(D40-Pad13)") (class "Default")
      (node (ref "D40") (pin "13") (pinfunction "13_13") (pintype "passive"))
    )
    (net (code "295") (name "unconnected-(D40-Pad14)") (class "Default")
      (node (ref "D40") (pin "14") (pinfunction "14_14") (pintype "passive"))
    )
    (net (code "296") (name "unconnected-(D40-Pad15)") (class "Default")
      (node (ref "D40") (pin "15") (pinfunction "15_15") (pintype "passive"))
    )
    (net (code "297") (name "unconnected-(D40-Pad21)") (class "Default")
      (node (ref "D40") (pin "21") (pinfunction "21_21") (pintype "passive"))
    )
    (net (code "298") (name "unconnected-(D40-Pad25)") (class "Default")
      (node (ref "D40") (pin "25") (pinfunction "25_25") (pintype "passive"))
    )
    (net (code "299") (name "unconnected-(D40-Pad27)") (class "Default")
      (node (ref "D40") (pin "27") (pinfunction "27_27") (pintype "passive"))
    )
    (net (code "300") (name "unconnected-(D40-Pad29)") (class "Default")
      (node (ref "D40") (pin "29") (pinfunction "29_29") (pintype "passive"))
    )
  )
)
